# isp.net
KiCad netlist of a schematic drawn in EAGLE
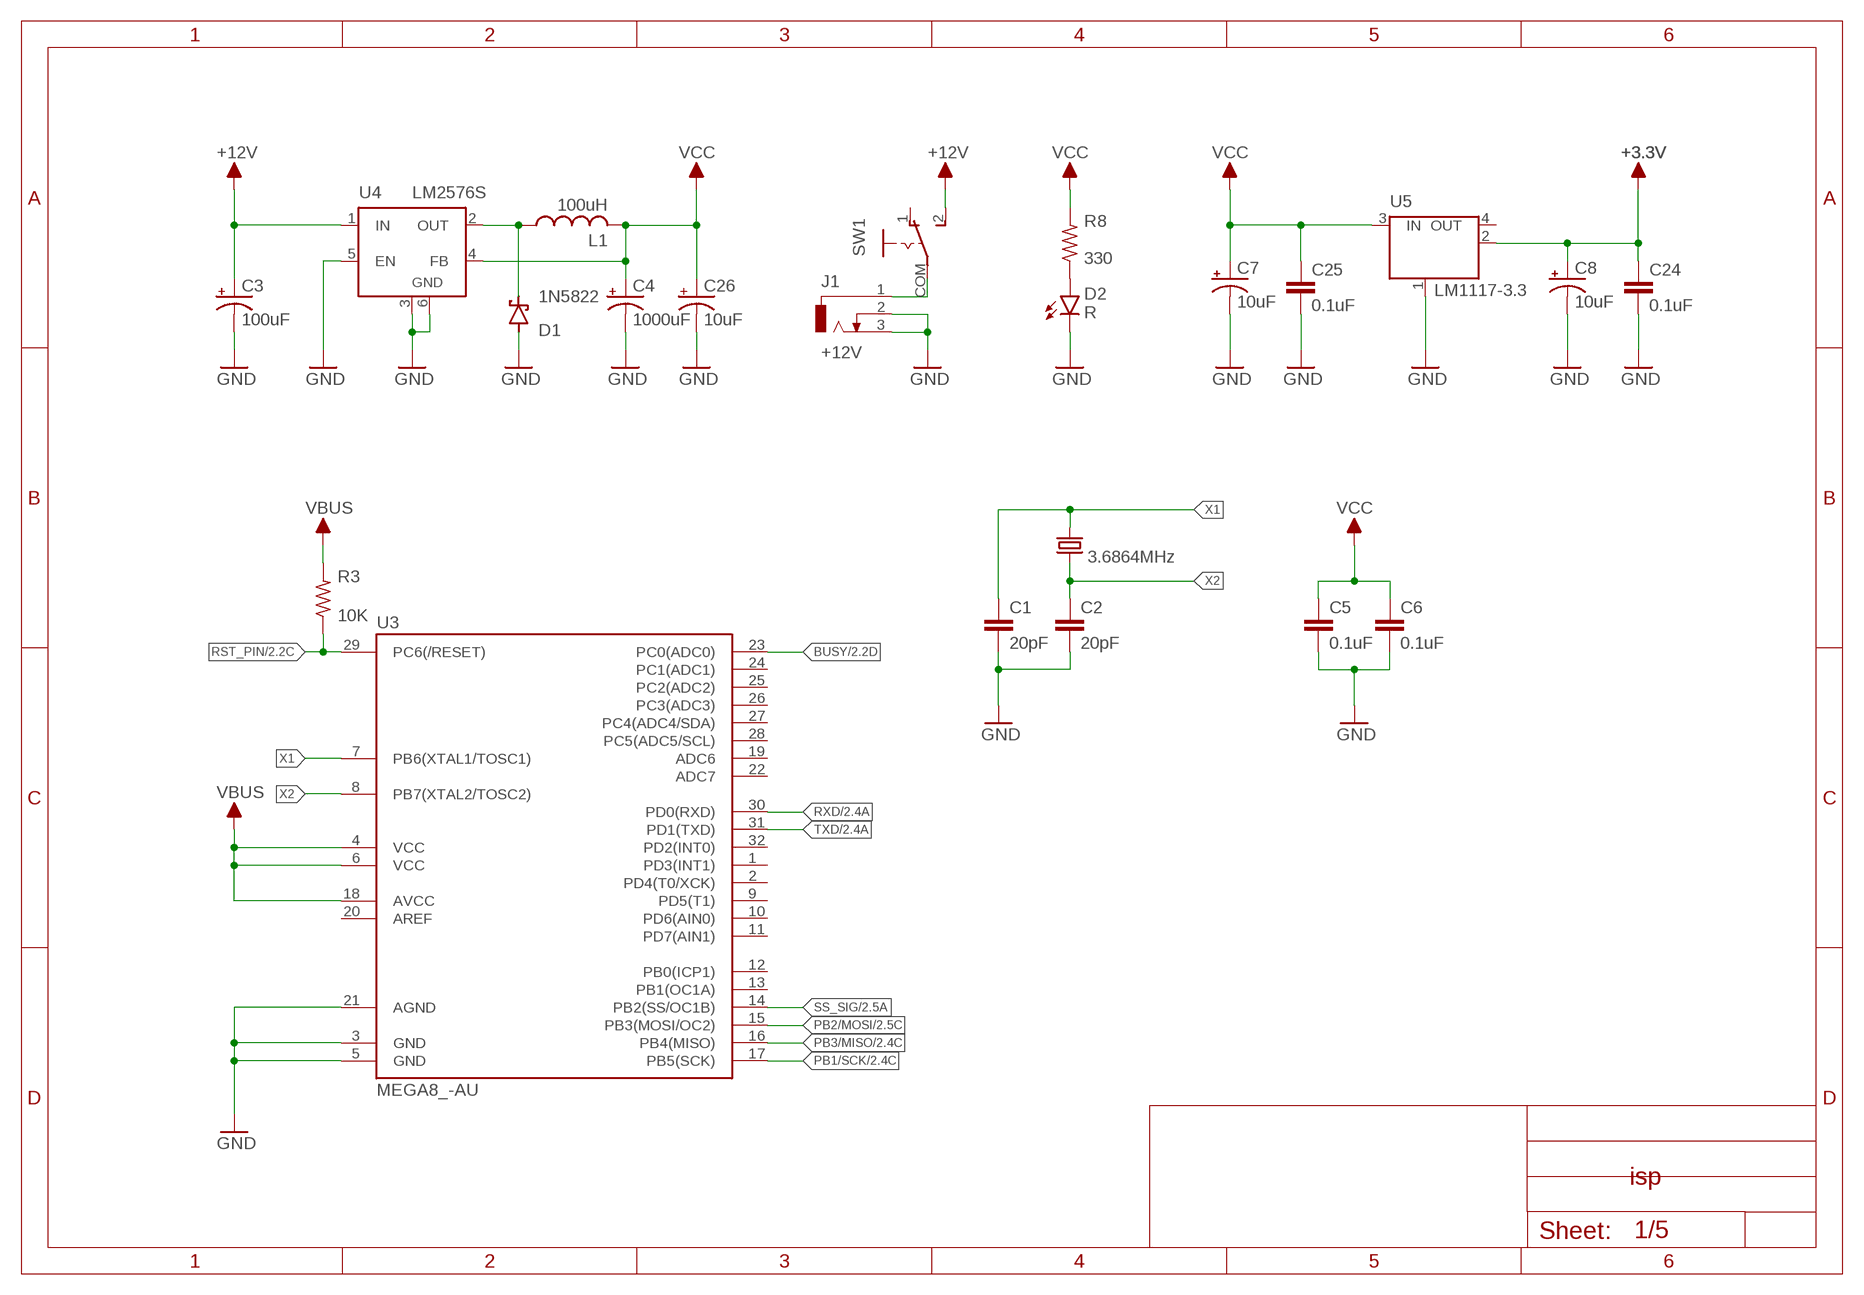
[diagram p0: schematic, sheet 1]
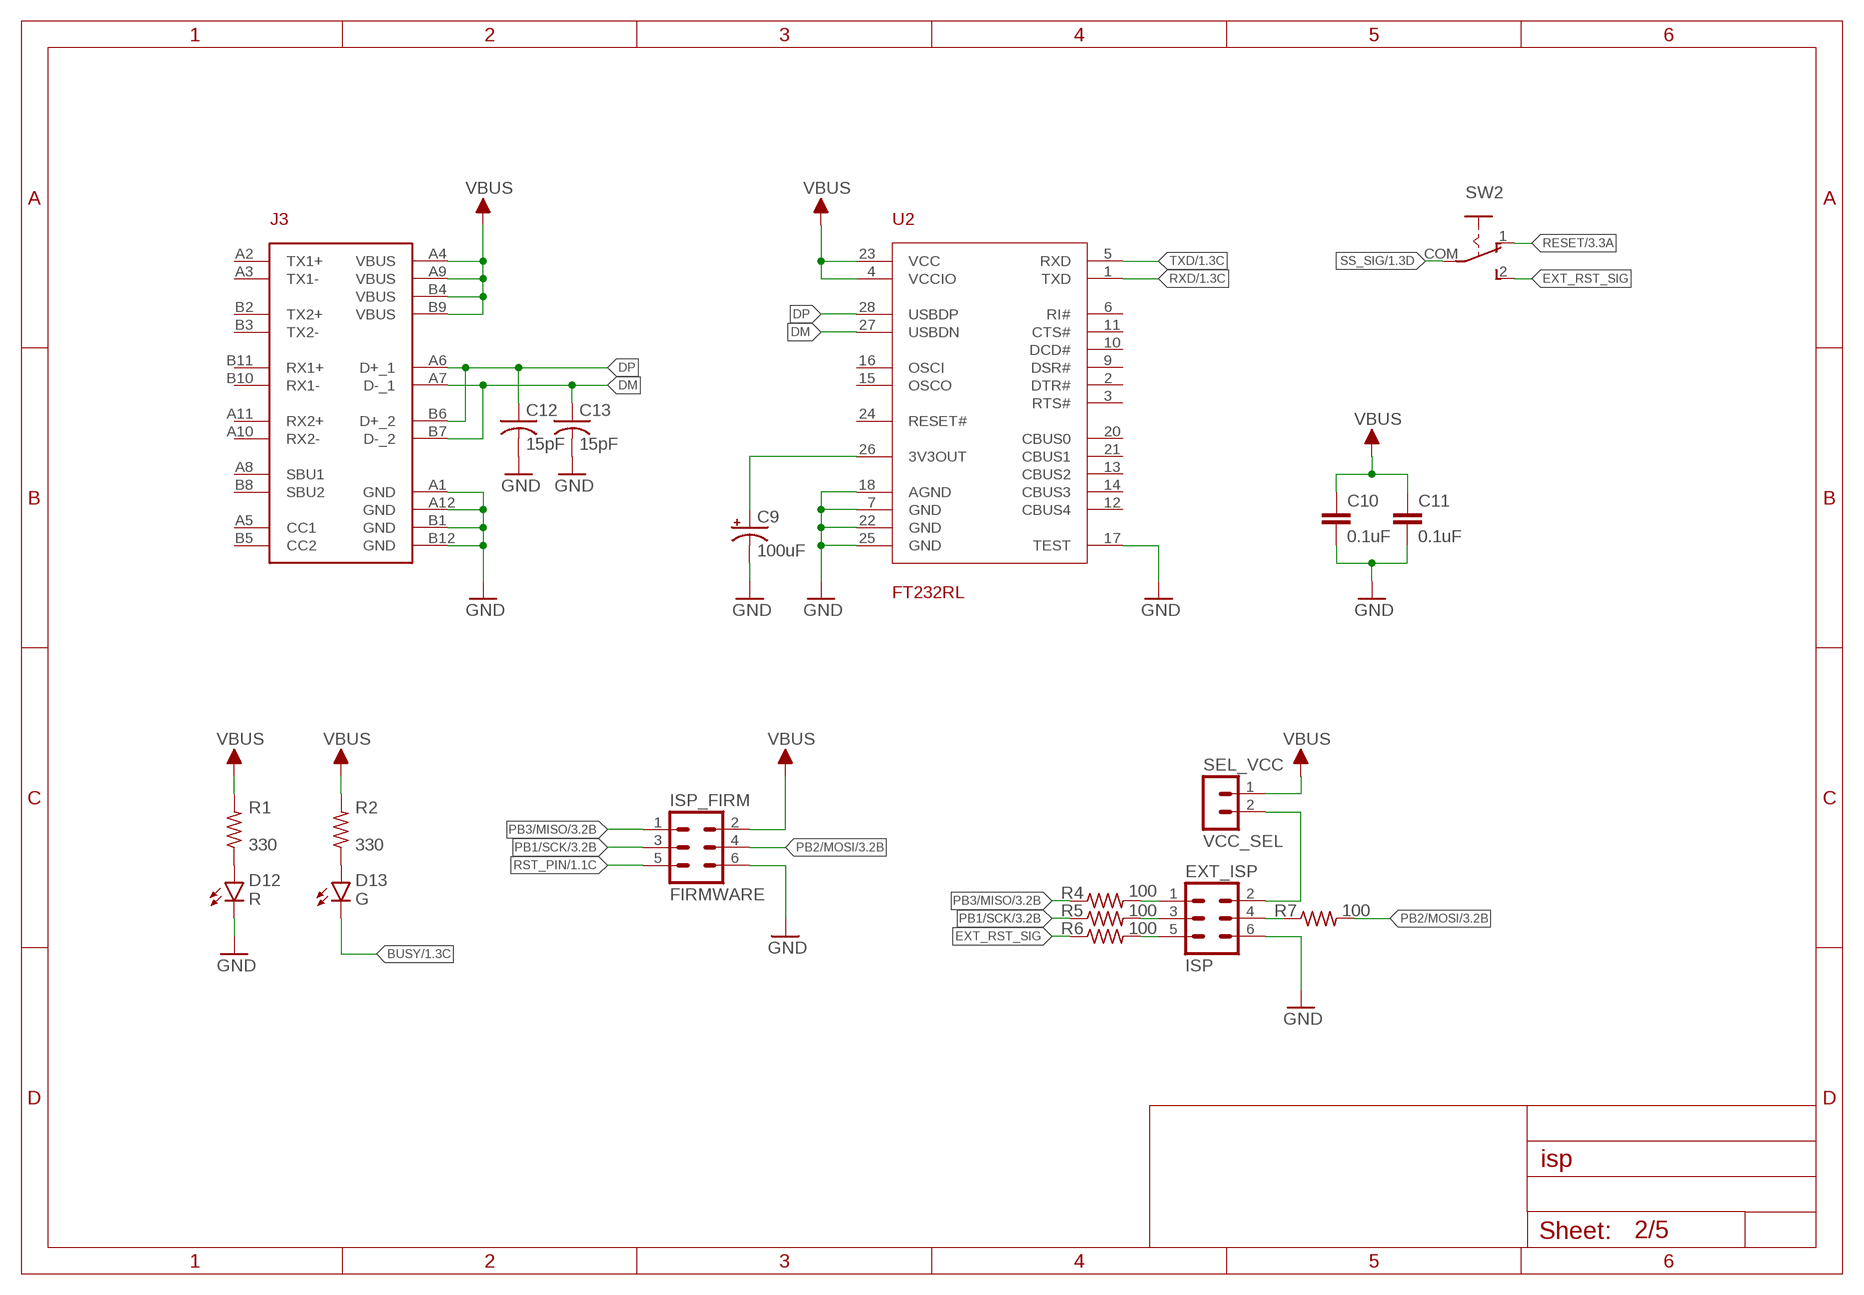
[diagram p1: schematic, sheet 2]
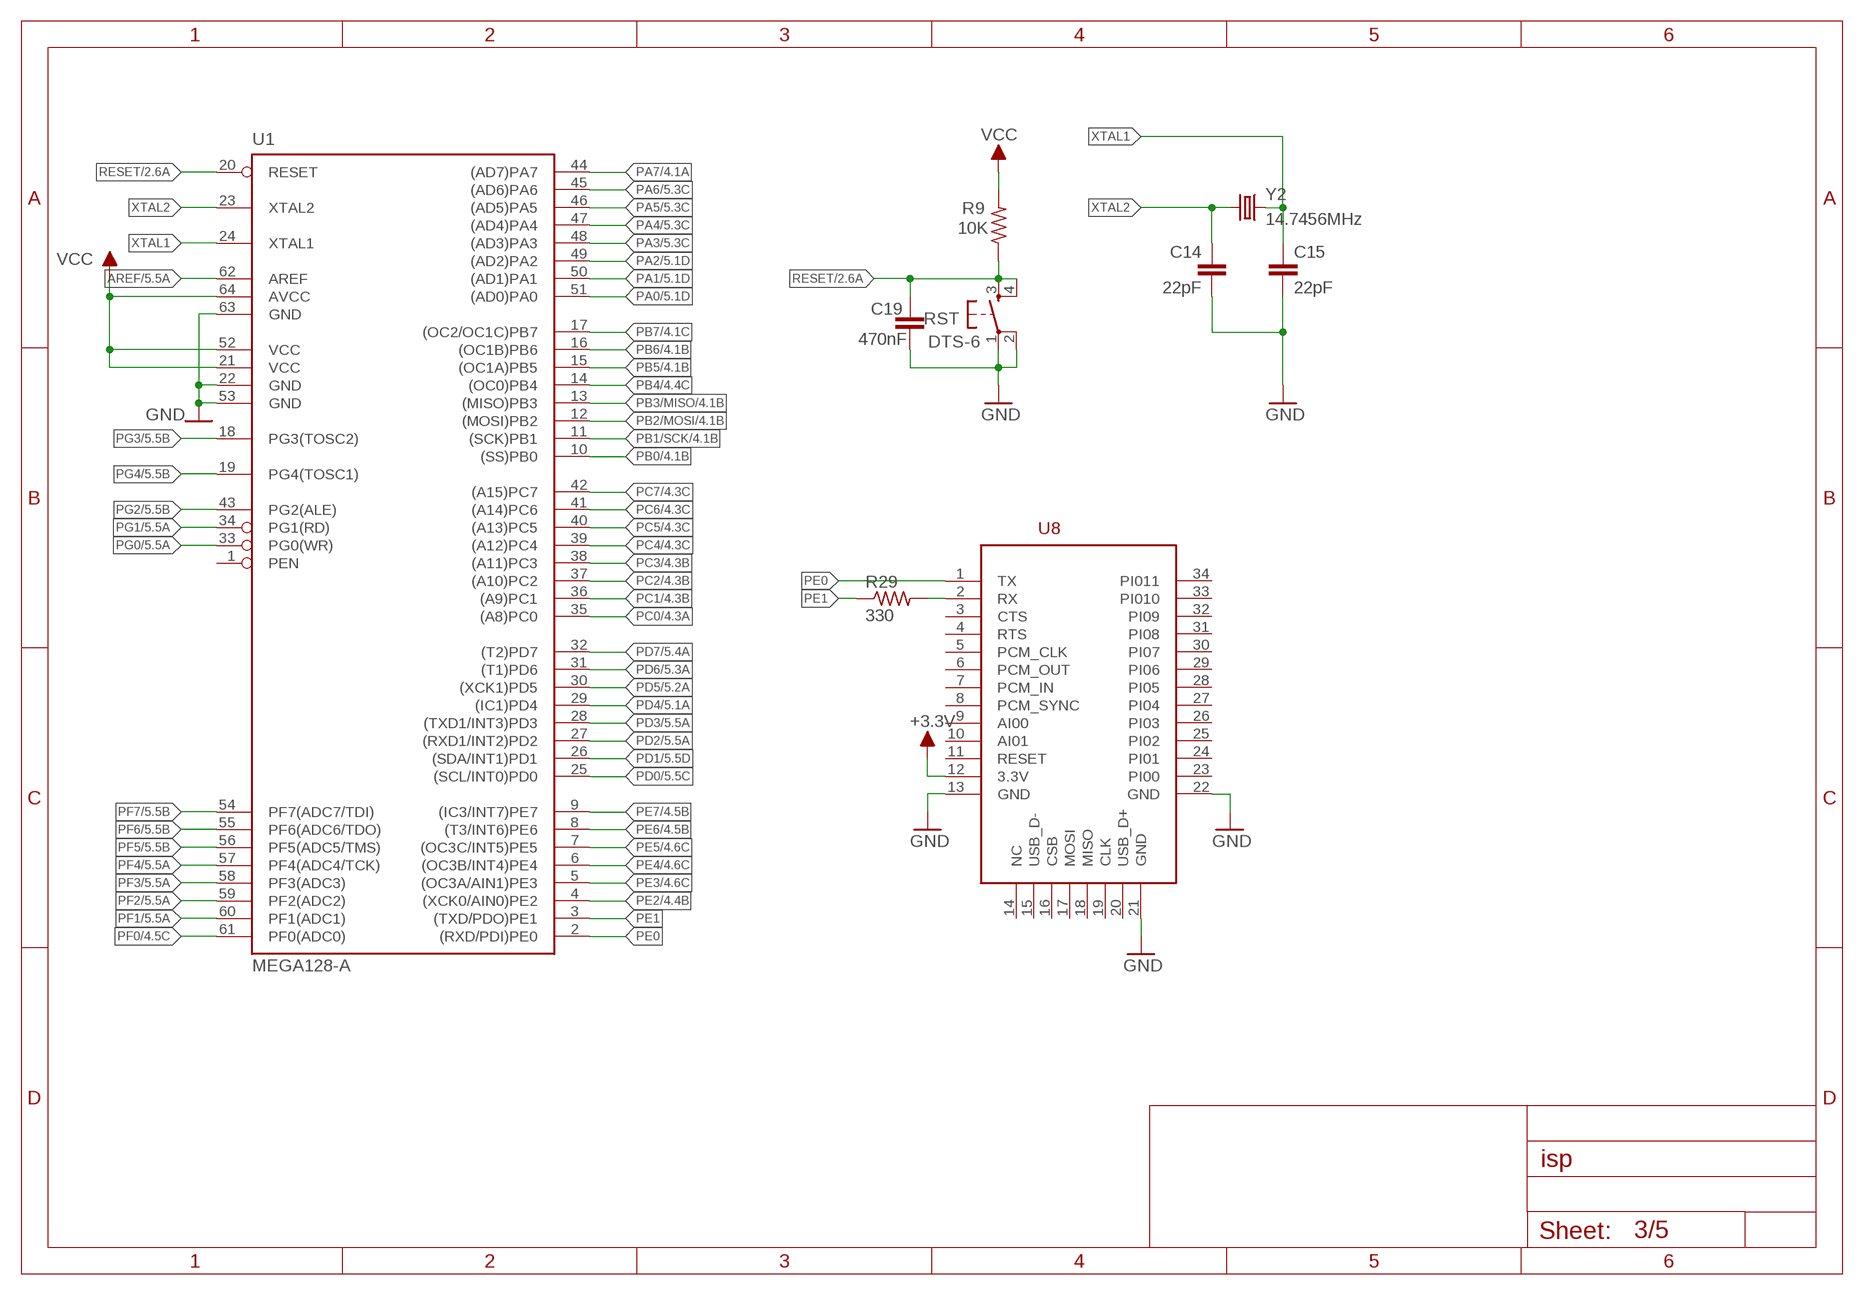
[diagram p2: schematic, sheet 3]
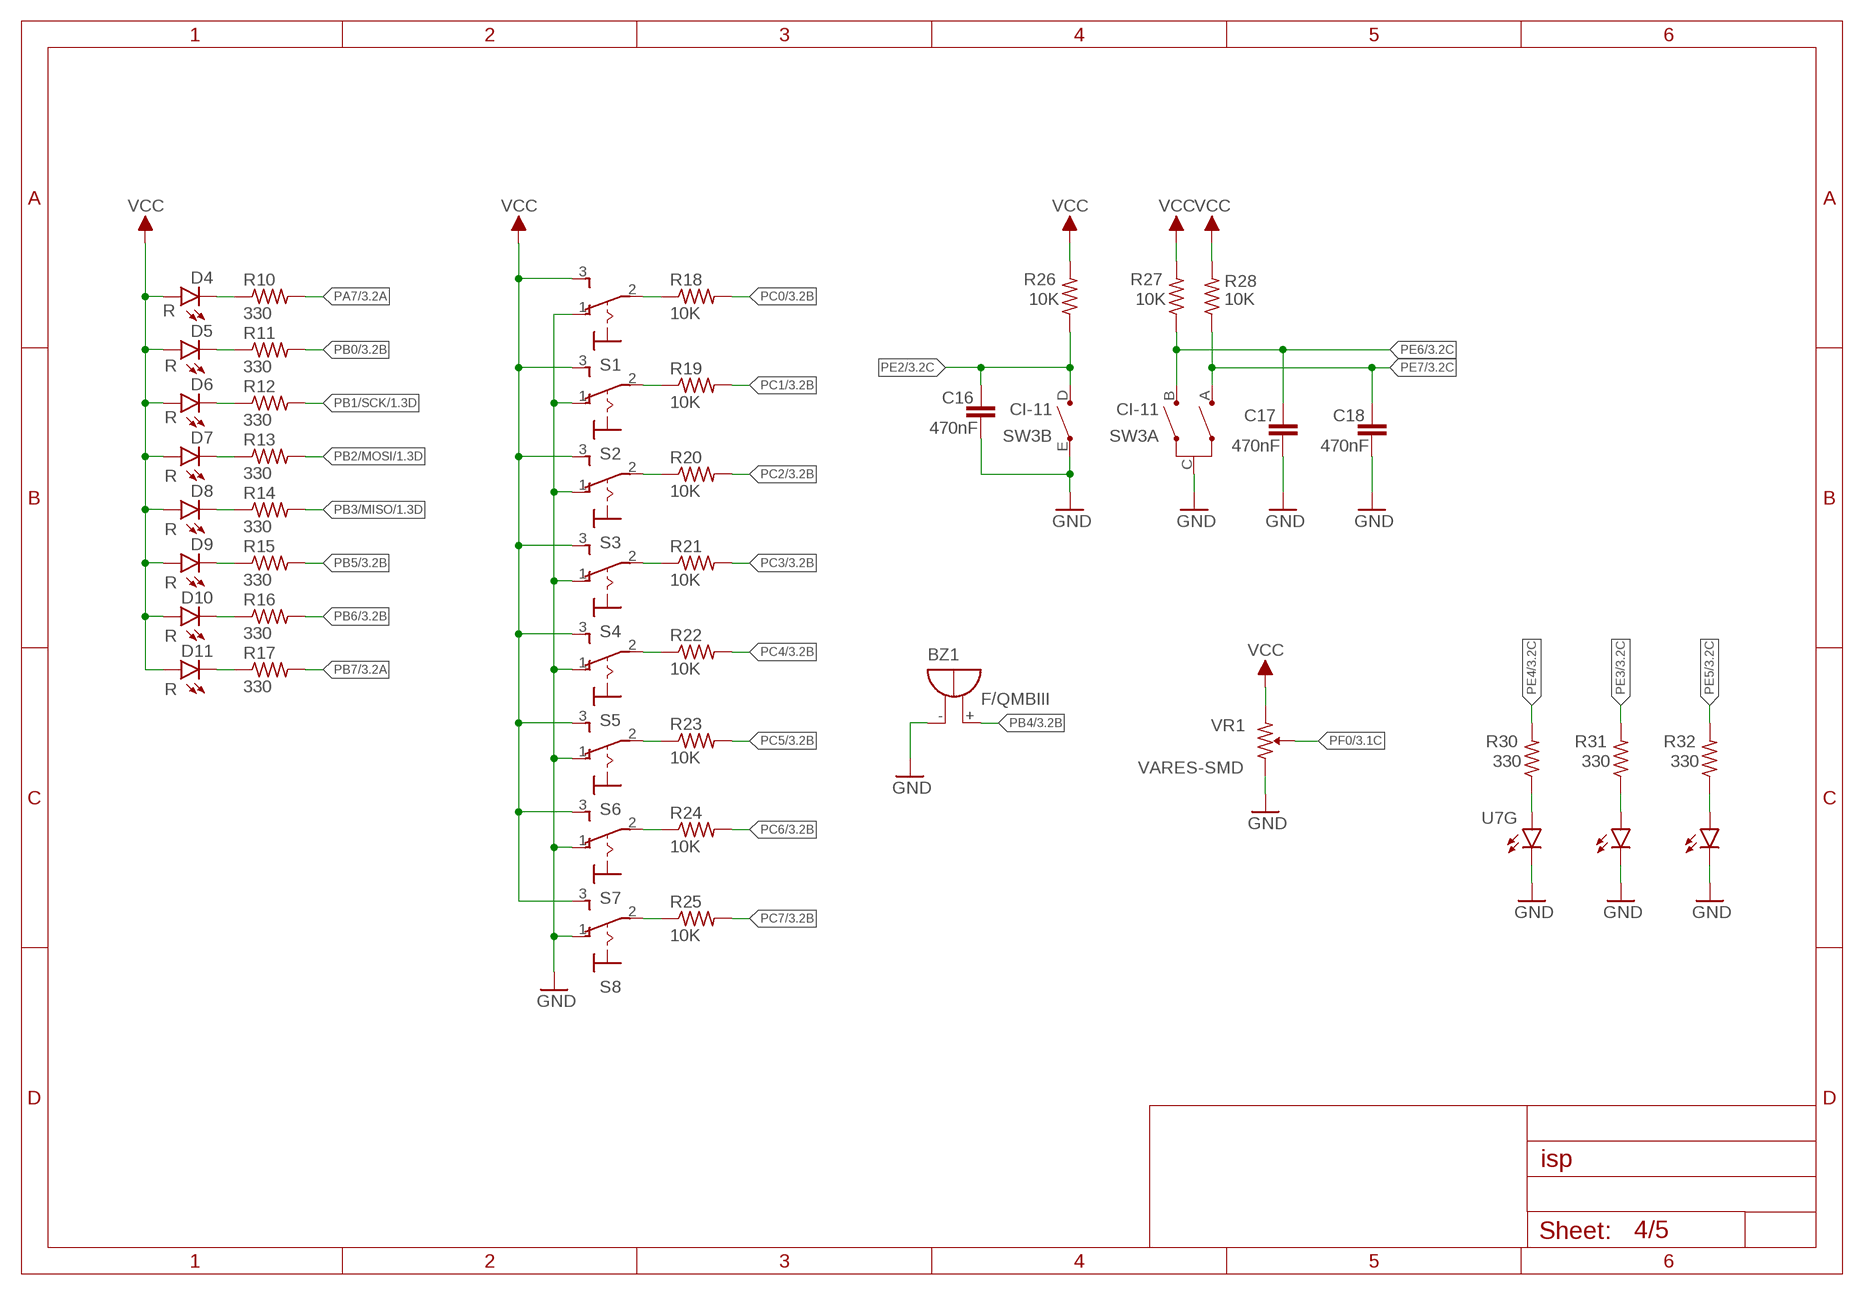
[diagram p3: schematic, sheet 4]
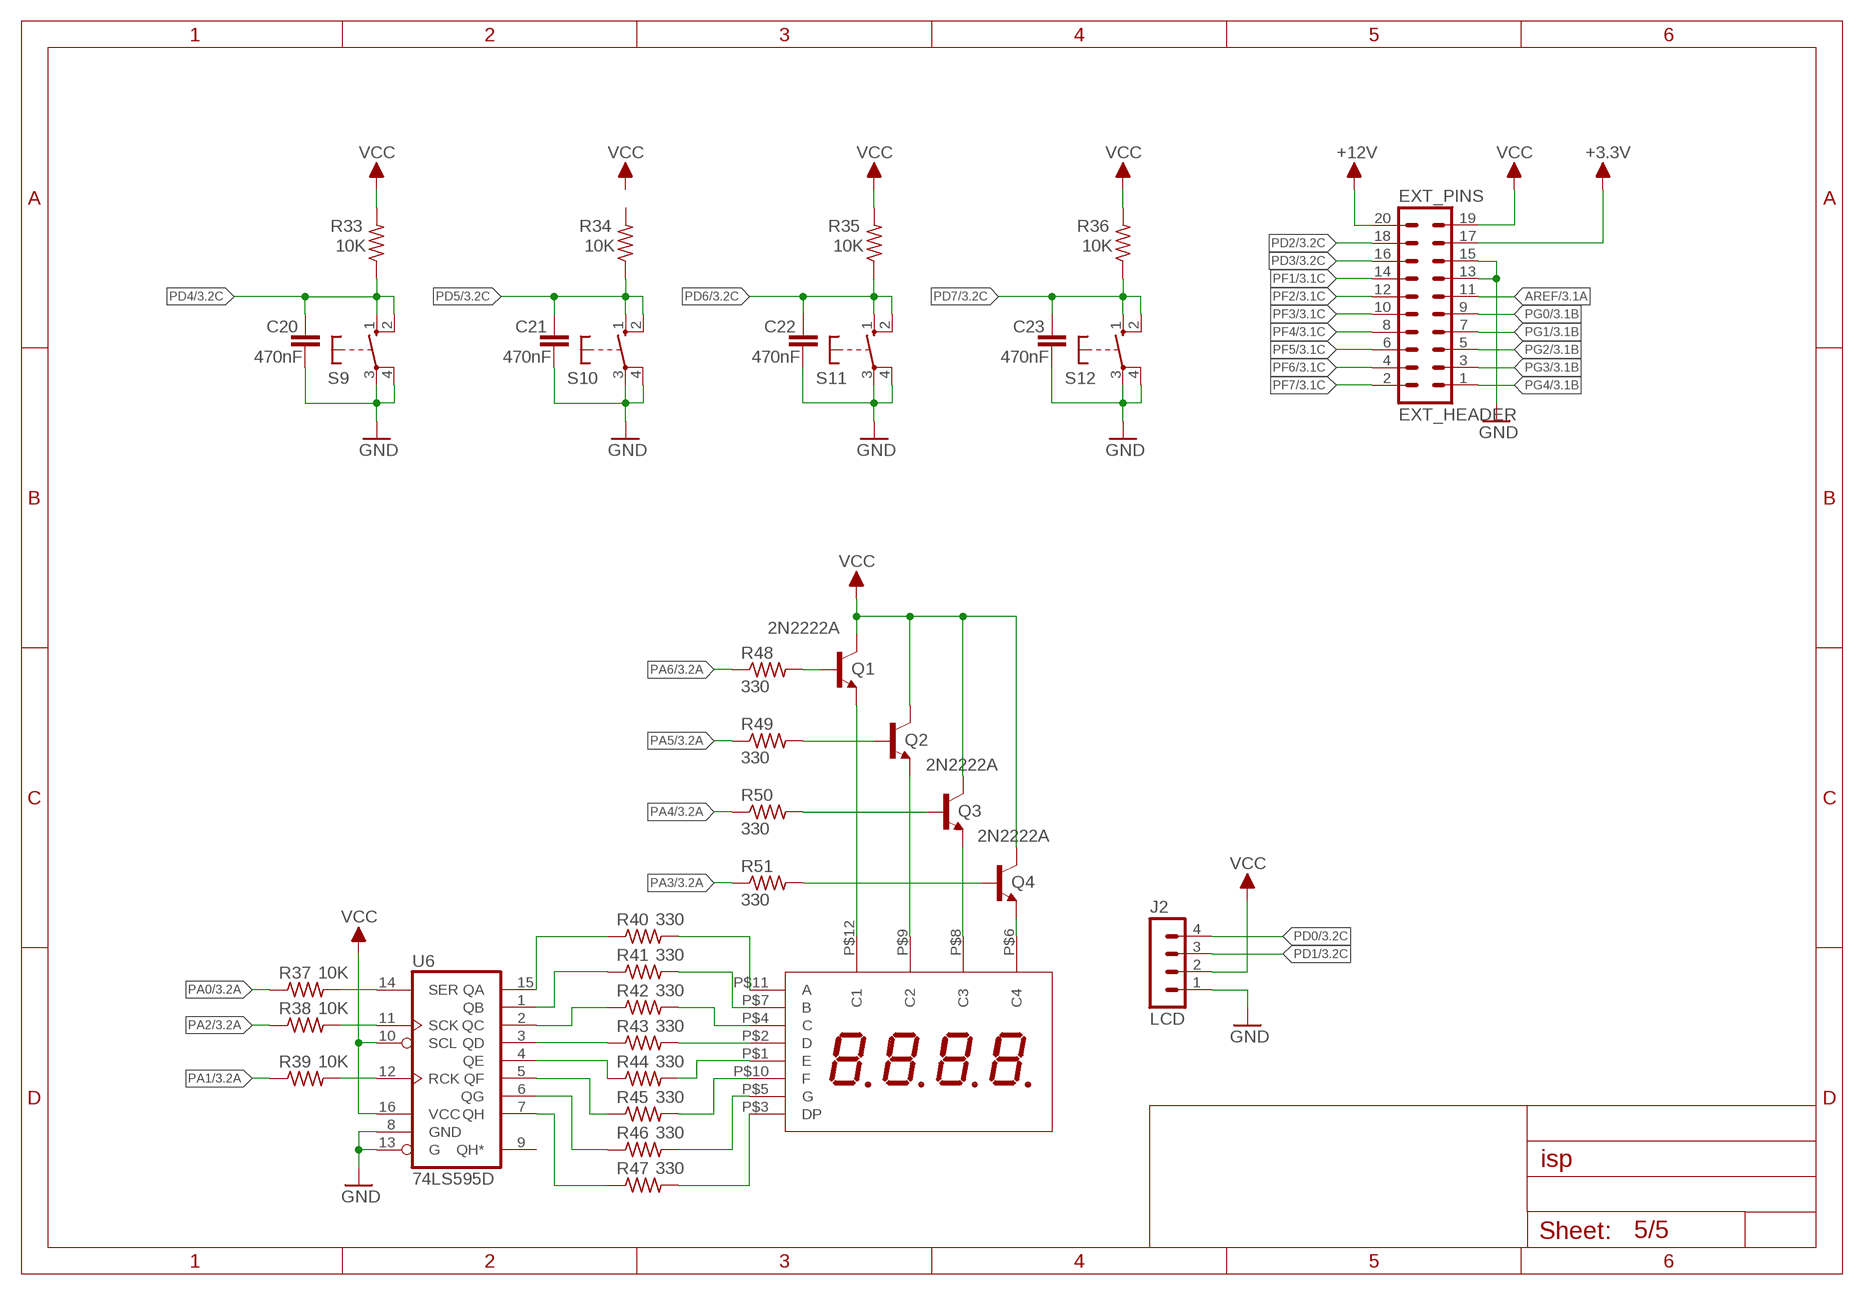
[diagram p4: schematic, sheet 5]

(export (version "E")
  (design (tool "Eeschema 10.0.6"))
  (components
    (comp (ref "BZ1")
      (value "F/QMBIII")
      (footprint "eagle-import:F_QMBIII")
      (libsource (lib "eagle-import") (part "F/QMBIII"))
    )
    (comp (ref "C16")
      (value "470nF")
      (footprint "eagle-import:C1206")
      (libsource (lib "eagle-import") (part "C-EUC1206"))
    )
    (comp (ref "C17")
      (value "470nF")
      (footprint "eagle-import:C1206")
      (libsource (lib "eagle-import") (part "C-EUC1206"))
    )
    (comp (ref "C18")
      (value "470nF")
      (footprint "eagle-import:C1206")
      (libsource (lib "eagle-import") (part "C-EUC1206"))
    )
    (comp (ref "D4")
      (value "R")
      (footprint "eagle-import:LED3MM")
      (libsource (lib "eagle-import") (part "LED3MM"))
    )
    (comp (ref "D5")
      (value "R")
      (footprint "eagle-import:LED3MM")
      (libsource (lib "eagle-import") (part "LED3MM"))
    )
    (comp (ref "D6")
      (value "R")
      (footprint "eagle-import:LED3MM")
      (libsource (lib "eagle-import") (part "LED3MM"))
    )
    (comp (ref "D7")
      (value "R")
      (footprint "eagle-import:LED3MM")
      (libsource (lib "eagle-import") (part "LED3MM"))
    )
    (comp (ref "D8")
      (value "R")
      (footprint "eagle-import:LED3MM")
      (libsource (lib "eagle-import") (part "LED3MM"))
    )
    (comp (ref "D9")
      (value "R")
      (footprint "eagle-import:LED3MM")
      (libsource (lib "eagle-import") (part "LED3MM"))
    )
    (comp (ref "D10")
      (value "R")
      (footprint "eagle-import:LED3MM")
      (libsource (lib "eagle-import") (part "LED3MM"))
    )
    (comp (ref "D11")
      (value "R")
      (footprint "eagle-import:LED3MM")
      (libsource (lib "eagle-import") (part "LED3MM"))
    )
    (comp (ref "R10")
      (value "330")
      (footprint "eagle-import:R0603")
      (libsource (lib "eagle-import") (part "R-US_R0603"))
    )
    (comp (ref "R11")
      (value "330")
      (footprint "eagle-import:R0603")
      (libsource (lib "eagle-import") (part "R-US_R0603"))
    )
    (comp (ref "R12")
      (value "330")
      (footprint "eagle-import:R0603")
      (libsource (lib "eagle-import") (part "R-US_R0603"))
    )
    (comp (ref "R13")
      (value "330")
      (footprint "eagle-import:R0603")
      (libsource (lib "eagle-import") (part "R-US_R0603"))
    )
    (comp (ref "R14")
      (value "330")
      (footprint "eagle-import:R0603")
      (libsource (lib "eagle-import") (part "R-US_R0603"))
    )
    (comp (ref "R15")
      (value "330")
      (footprint "eagle-import:R0603")
      (libsource (lib "eagle-import") (part "R-US_R0603"))
    )
    (comp (ref "R16")
      (value "330")
      (footprint "eagle-import:R0603")
      (libsource (lib "eagle-import") (part "R-US_R0603"))
    )
    (comp (ref "R17")
      (value "330")
      (footprint "eagle-import:R0603")
      (libsource (lib "eagle-import") (part "R-US_R0603"))
    )
    (comp (ref "R18")
      (value "10K")
      (footprint "eagle-import:R0603")
      (libsource (lib "eagle-import") (part "R-US_R0603"))
    )
    (comp (ref "R19")
      (value "10K")
      (footprint "eagle-import:R0603")
      (libsource (lib "eagle-import") (part "R-US_R0603"))
    )
    (comp (ref "R20")
      (value "10K")
      (footprint "eagle-import:R0603")
      (libsource (lib "eagle-import") (part "R-US_R0603"))
    )
    (comp (ref "R21")
      (value "10K")
      (footprint "eagle-import:R0603")
      (libsource (lib "eagle-import") (part "R-US_R0603"))
    )
    (comp (ref "R22")
      (value "10K")
      (footprint "eagle-import:R0603")
      (libsource (lib "eagle-import") (part "R-US_R0603"))
    )
    (comp (ref "R23")
      (value "10K")
      (footprint "eagle-import:R0603")
      (libsource (lib "eagle-import") (part "R-US_R0603"))
    )
    (comp (ref "R24")
      (value "10K")
      (footprint "eagle-import:R0603")
      (libsource (lib "eagle-import") (part "R-US_R0603"))
    )
    (comp (ref "R25")
      (value "10K")
      (footprint "eagle-import:R0603")
      (libsource (lib "eagle-import") (part "R-US_R0603"))
    )
    (comp (ref "R26")
      (value "10K")
      (footprint "eagle-import:R0603")
      (libsource (lib "eagle-import") (part "R-US_R0603"))
    )
    (comp (ref "R27")
      (value "10K")
      (footprint "eagle-import:R0603")
      (libsource (lib "eagle-import") (part "R-US_R0603"))
    )
    (comp (ref "R28")
      (value "10K")
      (footprint "eagle-import:R0603")
      (libsource (lib "eagle-import") (part "R-US_R0603"))
    )
    (comp (ref "R30")
      (value "330")
      (footprint "eagle-import:R0603")
      (libsource (lib "eagle-import") (part "R-US_R0603"))
    )
    (comp (ref "R31")
      (value "330")
      (footprint "eagle-import:R0603")
      (libsource (lib "eagle-import") (part "R-US_R0603"))
    )
    (comp (ref "R32")
      (value "330")
      (footprint "eagle-import:R0603")
      (libsource (lib "eagle-import") (part "R-US_R0603"))
    )
    (comp (ref "S1")
      (value "M9040P")
      (footprint "eagle-import:M9040P")
      (libsource (lib "eagle-import") (part "M9040P"))
    )
    (comp (ref "S2")
      (value "M9040P")
      (footprint "eagle-import:M9040P")
      (libsource (lib "eagle-import") (part "M9040P"))
    )
    (comp (ref "S3")
      (value "M9040P")
      (footprint "eagle-import:M9040P")
      (libsource (lib "eagle-import") (part "M9040P"))
    )
    (comp (ref "S4")
      (value "M9040P")
      (footprint "eagle-import:M9040P")
      (libsource (lib "eagle-import") (part "M9040P"))
    )
    (comp (ref "S5")
      (value "M9040P")
      (footprint "eagle-import:M9040P")
      (libsource (lib "eagle-import") (part "M9040P"))
    )
    (comp (ref "S6")
      (value "M9040P")
      (footprint "eagle-import:M9040P")
      (libsource (lib "eagle-import") (part "M9040P"))
    )
    (comp (ref "S7")
      (value "M9040P")
      (footprint "eagle-import:M9040P")
      (libsource (lib "eagle-import") (part "M9040P"))
    )
    (comp (ref "S8")
      (value "M9040P")
      (footprint "eagle-import:M9040P")
      (libsource (lib "eagle-import") (part "M9040P"))
    )
    (comp (ref "SW3")
      (value "CI-11")
      (footprint "eagle-import:CI-11")
      (libsource (lib "eagle-import") (part "CI-11"))
    )
    (comp (ref "U7")
      (value "LP2C63-ST-RGB-SR0")
      (footprint "eagle-import:LP2C63-ST-RGB-SR0")
      (libsource (lib "eagle-import") (part "LP2C63-ST-RGB-SR0"))
    )
    (comp (ref "VR1")
      (value "VARES-SMD")
      (footprint "eagle-import:VARES-SMD")
      (libsource (lib "eagle-import") (part "VARES-SMD"))
    )
    (comp (ref "C14")
      (value "22pF")
      (footprint "eagle-import:C0603")
      (libsource (lib "eagle-import") (part "C-EUC0603"))
    )
    (comp (ref "C15")
      (value "22pF")
      (footprint "eagle-import:C0603")
      (libsource (lib "eagle-import") (part "C-EUC0603"))
    )
    (comp (ref "C19")
      (value "470nF")
      (footprint "eagle-import:C1206")
      (libsource (lib "eagle-import") (part "C-EUC1206"))
    )
    (comp (ref "R9")
      (value "10K")
      (footprint "eagle-import:R0603")
      (libsource (lib "eagle-import") (part "R-US_R0603"))
    )
    (comp (ref "R29")
      (value "330")
      (footprint "eagle-import:R0603")
      (libsource (lib "eagle-import") (part "R-US_R0603"))
    )
    (comp (ref "RST")
      (value "DTS-6")
      (footprint "eagle-import:DTS-6")
      (libsource (lib "eagle-import") (part "DTS-6"))
    )
    (comp (ref "U1")
      (value "MEGA128-A")
      (footprint "eagle-import:TQFP64")
      (fields (field (name "MPN") "ATMEGA128-16AU"))
      (libsource (lib "eagle-import") (part "MEGA128-A"))
    )
    (comp (ref "U8")
      (value "HC06-SMD")
      (footprint "eagle-import:HC06-SMD")
      (libsource (lib "eagle-import") (part "HC06-SMD"))
    )
    (comp (ref "Y2")
      (value "14.7456MHz")
      (footprint "eagle-import:HC49UP")
      (libsource (lib "eagle-import") (part "CRYSTALHC49UP"))
    )
    (comp (ref "C1")
      (value "20pF")
      (footprint "eagle-import:C0603")
      (libsource (lib "eagle-import") (part "C-EUC0603"))
    )
    (comp (ref "C2")
      (value "20pF")
      (footprint "eagle-import:C0603")
      (libsource (lib "eagle-import") (part "C-EUC0603"))
    )
    (comp (ref "C3")
      (value "100uF")
      (footprint "eagle-import:153CLV-0807")
      (libsource (lib "eagle-import") (part "CPOL-US153CLV-0807"))
    )
    (comp (ref "C4")
      (value "1000uF")
      (footprint "eagle-import:MVG_K14")
      (libsource (lib "eagle-import") (part "MVG_K14"))
    )
    (comp (ref "C5")
      (value "0.1uF")
      (footprint "eagle-import:C0603")
      (libsource (lib "eagle-import") (part "C-EUC0603"))
    )
    (comp (ref "C6")
      (value "0.1uF")
      (footprint "eagle-import:C0603")
      (libsource (lib "eagle-import") (part "C-EUC0603"))
    )
    (comp (ref "C7")
      (value "10uF")
      (footprint "eagle-import:153CLV-0605")
      (libsource (lib "eagle-import") (part "CPOL-US153CLV-0605"))
    )
    (comp (ref "C8")
      (value "10uF")
      (footprint "eagle-import:153CLV-0605")
      (libsource (lib "eagle-import") (part "CPOL-US153CLV-0605"))
    )
    (comp (ref "C24")
      (value "0.1uF")
      (footprint "eagle-import:C0603")
      (libsource (lib "eagle-import") (part "C-EUC0603"))
    )
    (comp (ref "C25")
      (value "0.1uF")
      (footprint "eagle-import:C0603")
      (libsource (lib "eagle-import") (part "C-EUC0603"))
    )
    (comp (ref "C26")
      (value "10uF")
      (footprint "eagle-import:153CLV-0605")
      (libsource (lib "eagle-import") (part "CPOL-US153CLV-0605"))
    )
    (comp (ref "D1")
      (value "1N5822")
      (footprint "eagle-import:DO201T15")
      (libsource (lib "eagle-import") (part "15KEXXD"))
    )
    (comp (ref "D2")
      (value "R")
      (footprint "eagle-import:LED3MM")
      (libsource (lib "eagle-import") (part "LED3MM"))
    )
    (comp (ref "J1")
      (value "+12V")
      (footprint "eagle-import:DCJ0303")
      (libsource (lib "eagle-import") (part "DCJ0303"))
    )
    (comp (ref "L1")
      (value "100uH")
      (footprint "eagle-import:212-032T2")
      (libsource (lib "eagle-import") (part "SC1280S"))
    )
    (comp (ref "R3")
      (value "10K")
      (footprint "eagle-import:R0603")
      (libsource (lib "eagle-import") (part "R-US_R0603"))
    )
    (comp (ref "R8")
      (value "330")
      (footprint "eagle-import:R0603")
      (libsource (lib "eagle-import") (part "R-US_R0603"))
    )
    (comp (ref "SW1")
      (value "SLIDE-SW-DIP")
      (footprint "eagle-import:SLIDE-SW-DIP-SHIELD")
      (libsource (lib "eagle-import") (part "SLIDE-SW-DIP"))
    )
    (comp (ref "U3")
      (value "MEGA8_-AU")
      (footprint "eagle-import:TQFP32-08")
      (libsource (lib "eagle-import") (part "MEGA8_-AU"))
    )
    (comp (ref "U4")
      (value "LM2576S")
      (footprint "eagle-import:TO263-5")
      (libsource (lib "eagle-import") (part "LM2596S"))
    )
    (comp (ref "U5")
      (value "LM1117-3.3")
      (footprint "eagle-import:SOT223")
      (libsource (lib "eagle-import") (part "MC33269ST-3.3T3"))
    )
    (comp (ref "Y1")
      (value "3.6864MHz")
      (footprint "eagle-import:HC49UP")
      (libsource (lib "eagle-import") (part "CRYSTALHC49UP"))
    )
    (comp (ref "C20")
      (value "470nF")
      (footprint "eagle-import:C1206")
      (libsource (lib "eagle-import") (part "C-EUC1206"))
    )
    (comp (ref "C21")
      (value "470nF")
      (footprint "eagle-import:C1206")
      (libsource (lib "eagle-import") (part "C-EUC1206"))
    )
    (comp (ref "C22")
      (value "470nF")
      (footprint "eagle-import:C1206")
      (libsource (lib "eagle-import") (part "C-EUC1206"))
    )
    (comp (ref "C23")
      (value "470nF")
      (footprint "eagle-import:C1206")
      (libsource (lib "eagle-import") (part "C-EUC1206"))
    )
    (comp (ref "D3")
      (value "4CH_FND-DIP")
      (footprint "eagle-import:4CH_FND-DIP")
      (libsource (lib "eagle-import") (part "4CH_FND-DIP"))
    )
    (comp (ref "EXT_PINS")
      (value "EXT_HEADER")
      (footprint "eagle-import:MA10-2")
      (libsource (lib "eagle-import") (part "MA10-2"))
    )
    (comp (ref "J2")
      (value "LCD")
      (footprint "eagle-import:MA04-1")
      (libsource (lib "eagle-import") (part "MA04-1"))
    )
    (comp (ref "Q1")
      (value "2N2222A")
      (footprint "eagle-import:TO92-EBC")
      (libsource (lib "eagle-import") (part "-NPN-TO92-EBC"))
    )
    (comp (ref "Q2")
      (value "2N2222A")
      (footprint "eagle-import:TO92-EBC")
      (libsource (lib "eagle-import") (part "-NPN-TO92-EBC"))
    )
    (comp (ref "Q3")
      (value "2N2222A")
      (footprint "eagle-import:TO92-EBC")
      (libsource (lib "eagle-import") (part "-NPN-TO92-EBC"))
    )
    (comp (ref "Q4")
      (value "2N2222A")
      (footprint "eagle-import:TO92-EBC")
      (libsource (lib "eagle-import") (part "-NPN-TO92-EBC"))
    )
    (comp (ref "R33")
      (value "10K")
      (footprint "eagle-import:R0603")
      (libsource (lib "eagle-import") (part "R-US_R0603"))
    )
    (comp (ref "R34")
      (value "10K")
      (footprint "eagle-import:R0603")
      (libsource (lib "eagle-import") (part "R-US_R0603"))
    )
    (comp (ref "R35")
      (value "10K")
      (footprint "eagle-import:R0603")
      (libsource (lib "eagle-import") (part "R-US_R0603"))
    )
    (comp (ref "R36")
      (value "10K")
      (footprint "eagle-import:R0603")
      (libsource (lib "eagle-import") (part "R-US_R0603"))
    )
    (comp (ref "R37")
      (value "10K")
      (footprint "eagle-import:R0603")
      (libsource (lib "eagle-import") (part "R-US_R0603"))
    )
    (comp (ref "R38")
      (value "10K")
      (footprint "eagle-import:R0603")
      (libsource (lib "eagle-import") (part "R-US_R0603"))
    )
    (comp (ref "R39")
      (value "10K")
      (footprint "eagle-import:R0603")
      (libsource (lib "eagle-import") (part "R-US_R0603"))
    )
    (comp (ref "R40")
      (value "330")
      (footprint "eagle-import:R0603")
      (libsource (lib "eagle-import") (part "R-US_R0603"))
    )
    (comp (ref "R41")
      (value "330")
      (footprint "eagle-import:R0603")
      (libsource (lib "eagle-import") (part "R-US_R0603"))
    )
    (comp (ref "R42")
      (value "330")
      (footprint "eagle-import:R0603")
      (libsource (lib "eagle-import") (part "R-US_R0603"))
    )
    (comp (ref "R43")
      (value "330")
      (footprint "eagle-import:R0603")
      (libsource (lib "eagle-import") (part "R-US_R0603"))
    )
    (comp (ref "R44")
      (value "330")
      (footprint "eagle-import:R0603")
      (libsource (lib "eagle-import") (part "R-US_R0603"))
    )
    (comp (ref "R45")
      (value "330")
      (footprint "eagle-import:R0603")
      (libsource (lib "eagle-import") (part "R-US_R0603"))
    )
    (comp (ref "R46")
      (value "330")
      (footprint "eagle-import:R0603")
      (libsource (lib "eagle-import") (part "R-US_R0603"))
    )
    (comp (ref "R47")
      (value "330")
      (footprint "eagle-import:R0603")
      (libsource (lib "eagle-import") (part "R-US_R0603"))
    )
    (comp (ref "R48")
      (value "330")
      (footprint "eagle-import:R0603")
      (libsource (lib "eagle-import") (part "R-US_R0603"))
    )
    (comp (ref "R49")
      (value "330")
      (footprint "eagle-import:R0603")
      (libsource (lib "eagle-import") (part "R-US_R0603"))
    )
    (comp (ref "R50")
      (value "330")
      (footprint "eagle-import:R0603")
      (libsource (lib "eagle-import") (part "R-US_R0603"))
    )
    (comp (ref "R51")
      (value "330")
      (footprint "eagle-import:R0603")
      (libsource (lib "eagle-import") (part "R-US_R0603"))
    )
    (comp (ref "S9")
      (value "RACON12")
      (footprint "eagle-import:RACON12")
      (libsource (lib "eagle-import") (part "RACON12"))
    )
    (comp (ref "S10")
      (value "RACON12")
      (footprint "eagle-import:RACON12")
      (libsource (lib "eagle-import") (part "RACON12"))
    )
    (comp (ref "S11")
      (value "RACON12")
      (footprint "eagle-import:RACON12")
      (libsource (lib "eagle-import") (part "RACON12"))
    )
    (comp (ref "S12")
      (value "RACON12")
      (footprint "eagle-import:RACON12")
      (libsource (lib "eagle-import") (part "RACON12"))
    )
    (comp (ref "U6")
      (value "74LS595D")
      (footprint "eagle-import:SO16")
      (libsource (lib "eagle-import") (part "74595DLS"))
    )
    (comp (ref "C9")
      (value "100uF")
      (footprint "eagle-import:153CLV-0807")
      (libsource (lib "eagle-import") (part "CPOL-US153CLV-0807"))
    )
    (comp (ref "C10")
      (value "0.1uF")
      (footprint "eagle-import:C0603")
      (libsource (lib "eagle-import") (part "C-EUC0603"))
    )
    (comp (ref "C11")
      (value "0.1uF")
      (footprint "eagle-import:C0603")
      (libsource (lib "eagle-import") (part "C-EUC0603"))
    )
    (comp (ref "C12")
      (value "15pF")
      (footprint "eagle-import:C0603")
      (libsource (lib "eagle-import") (part "C-USC0603"))
    )
    (comp (ref "C13")
      (value "15pF")
      (footprint "eagle-import:C0603")
      (libsource (lib "eagle-import") (part "C-USC0603"))
    )
    (comp (ref "D12")
      (value "R")
      (footprint "eagle-import:LED3MM")
      (libsource (lib "eagle-import") (part "LED3MM"))
    )
    (comp (ref "D13")
      (value "G")
      (footprint "eagle-import:LED3MM")
      (libsource (lib "eagle-import") (part "LED3MM"))
    )
    (comp (ref "EXT_ISP")
      (value "ISP")
      (footprint "eagle-import:ML6")
      (libsource (lib "eagle-import") (part "ML6"))
    )
    (comp (ref "ISP_FIRM")
      (value "FIRMWARE")
      (footprint "eagle-import:MA03-2")
      (libsource (lib "eagle-import") (part "MA03-2"))
    )
    (comp (ref "J3")
      (value "USB-C-SMD")
      (footprint "eagle-import:USB3.1-C-SMD")
      (libsource (lib "eagle-import") (part "USB-C-SMD"))
    )
    (comp (ref "R1")
      (value "330")
      (footprint "eagle-import:R0603")
      (libsource (lib "eagle-import") (part "R-US_R0603"))
    )
    (comp (ref "R2")
      (value "330")
      (footprint "eagle-import:R0603")
      (libsource (lib "eagle-import") (part "R-US_R0603"))
    )
    (comp (ref "R4")
      (value "100")
      (footprint "eagle-import:R0603")
      (libsource (lib "eagle-import") (part "R-US_R0603"))
    )
    (comp (ref "R5")
      (value "100")
      (footprint "eagle-import:R0603")
      (libsource (lib "eagle-import") (part "R-US_R0603"))
    )
    (comp (ref "R6")
      (value "100")
      (footprint "eagle-import:R0603")
      (libsource (lib "eagle-import") (part "R-US_R0603"))
    )
    (comp (ref "R7")
      (value "100")
      (footprint "eagle-import:R0603")
      (libsource (lib "eagle-import") (part "R-US_R0603"))
    )
    (comp (ref "SEL_VCC")
      (value "VCC_SEL")
      (footprint "eagle-import:MA02-1")
      (libsource (lib "eagle-import") (part "MA02-1"))
    )
    (comp (ref "SW2")
      (value "SLIDE-SW-DIP")
      (footprint "eagle-import:SLIDE-SW-DIP-SHIELD")
      (libsource (lib "eagle-import") (part "SLIDE-SW-DIP"))
    )
    (comp (ref "U2")
      (value "FT232RL")
      (footprint "eagle-import:SSOP28")
      (libsource (lib "eagle-import") (part "FT232RL"))
    )
  )
  (nets
    (net (code "1") (name "+3.3V") (class "Default")
      (node (ref "C24") (pin "1") (pinfunction "1_1") (pintype "passive"))
      (node (ref "C8") (pin "+") (pinfunction "+_+") (pintype "passive"))
      (node (ref "EXT_PINS") (pin "17") (pinfunction "17_17") (pintype "passive"))
      (node (ref "U5") (pin "2") (pinfunction "OUT_2") (pintype "passive"))
      (node (ref "U8") (pin "12") (pinfunction "3.3V_12") (pintype "power_in"))
    )
    (net (code "2") (name "+12V") (class "Default")
      (node (ref "C3") (pin "+") (pinfunction "+_+") (pintype "passive"))
      (node (ref "EXT_PINS") (pin "20") (pinfunction "20_20") (pintype "passive"))
      (node (ref "SW1") (pin "2") (pinfunction "2_2") (pintype "passive"))
      (node (ref "U4") (pin "1") (pinfunction "IN_1") (pintype "input"))
    )
    (net (code "3") (name "AREF") (class "Default")
      (node (ref "EXT_PINS") (pin "11") (pinfunction "11_11") (pintype "passive"))
      (node (ref "U1") (pin "62") (pinfunction "AREF_62") (pintype "passive"))
    )
    (net (code "4") (name "BUSY") (class "Default")
      (node (ref "D13") (pin "K") (pinfunction "C_K") (pintype "passive"))
      (node (ref "U3") (pin "23") (pinfunction "PC0(ADC0)_23") (pintype "bidirectional"))
    )
    (net (code "5") (name "DM") (class "Default")
      (node (ref "C13") (pin "1") (pinfunction "1_1") (pintype "passive"))
      (node (ref "J3") (pin "A7") (pinfunction "D-_1_A7") (pintype "bidirectional"))
      (node (ref "J3") (pin "B7") (pinfunction "D-_2_B7") (pintype "bidirectional"))
      (node (ref "U2") (pin "27") (pinfunction "USBDN_27") (pintype "bidirectional"))
    )
    (net (code "6") (name "DP") (class "Default")
      (node (ref "C12") (pin "1") (pinfunction "1_1") (pintype "passive"))
      (node (ref "J3") (pin "A6") (pinfunction "D+_1_A6") (pintype "bidirectional"))
      (node (ref "J3") (pin "B6") (pinfunction "D+_2_B6") (pintype "bidirectional"))
      (node (ref "U2") (pin "28") (pinfunction "USBDP_28") (pintype "bidirectional"))
    )
    (net (code "7") (name "EXT_RST_SIG") (class "Default")
      (node (ref "R6") (pin "1") (pinfunction "1_1") (pintype "passive"))
      (node (ref "SW2") (pin "2") (pinfunction "2_2") (pintype "passive"))
    )
    (net (code "8") (name "GND") (class "Default")
      (node (ref "BZ1") (pin "-") (pinfunction "+_-") (pintype "passive"))
      (node (ref "C1") (pin "2") (pinfunction "2_2") (pintype "passive"))
      (node (ref "C10") (pin "2") (pinfunction "2_2") (pintype "passive"))
      (node (ref "C11") (pin "2") (pinfunction "2_2") (pintype "passive"))
      (node (ref "C12") (pin "2") (pinfunction "2_2") (pintype "passive"))
      (node (ref "C13") (pin "2") (pinfunction "2_2") (pintype "passive"))
      (node (ref "C14") (pin "1") (pinfunction "1_1") (pintype "passive"))
      (node (ref "C15") (pin "2") (pinfunction "2_2") (pintype "passive"))
      (node (ref "C16") (pin "2") (pinfunction "2_2") (pintype "passive"))
      (node (ref "C17") (pin "2") (pinfunction "2_2") (pintype "passive"))
      (node (ref "C18") (pin "2") (pinfunction "2_2") (pintype "passive"))
      (node (ref "C19") (pin "2") (pinfunction "2_2") (pintype "passive"))
      (node (ref "C2") (pin "2") (pinfunction "2_2") (pintype "passive"))
      (node (ref "C20") (pin "2") (pinfunction "2_2") (pintype "passive"))
      (node (ref "C21") (pin "2") (pinfunction "2_2") (pintype "passive"))
      (node (ref "C22") (pin "2") (pinfunction "2_2") (pintype "passive"))
      (node (ref "C23") (pin "2") (pinfunction "2_2") (pintype "passive"))
      (node (ref "C24") (pin "2") (pinfunction "2_2") (pintype "passive"))
      (node (ref "C25") (pin "2") (pinfunction "2_2") (pintype "passive"))
      (node (ref "C26") (pin "-") (pinfunction "-_-") (pintype "passive"))
      (node (ref "C3") (pin "-") (pinfunction "-_-") (pintype "passive"))
      (node (ref "C4") (pin "-") (pinfunction "-_-") (pintype "passive"))
      (node (ref "C5") (pin "2") (pinfunction "2_2") (pintype "passive"))
      (node (ref "C6") (pin "2") (pinfunction "2_2") (pintype "passive"))
      (node (ref "C7") (pin "-") (pinfunction "-_-") (pintype "passive"))
      (node (ref "C8") (pin "-") (pinfunction "-_-") (pintype "passive"))
      (node (ref "C9") (pin "-") (pinfunction "-_-") (pintype "passive"))
      (node (ref "D1") (pin "A") (pinfunction "A_A") (pintype "passive"))
      (node (ref "D12") (pin "K") (pinfunction "C_K") (pintype "passive"))
      (node (ref "D2") (pin "K") (pinfunction "C_K") (pintype "passive"))
      (node (ref "EXT_ISP") (pin "6") (pinfunction "6_6") (pintype "passive"))
      (node (ref "EXT_PINS") (pin "13") (pinfunction "13_13") (pintype "passive"))
      (node (ref "EXT_PINS") (pin "15") (pinfunction "15_15") (pintype "passive"))
      (node (ref "ISP_FIRM") (pin "6") (pinfunction "6_6") (pintype "passive"))
      (node (ref "J1") (pin "2") (pinfunction "2_2") (pintype "passive"))
      (node (ref "J1") (pin "3") (pinfunction "3_3") (pintype "passive"))
      (node (ref "J2") (pin "1") (pinfunction "1_1") (pintype "passive"))
      (node (ref "J3") (pin "A1") (pinfunction "GND_A1") (pintype "bidirectional"))
      (node (ref "J3") (pin "A12") (pinfunction "GND_A12") (pintype "bidirectional"))
      (node (ref "J3") (pin "B1") (pinfunction "GND_B1") (pintype "bidirectional"))
      (node (ref "J3") (pin "B12") (pinfunction "GND_B12") (pintype "bidirectional"))
      (node (ref "RST") (pin "1") (pinfunction "1_1") (pintype "passive"))
      (node (ref "RST") (pin "2") (pinfunction "2_2") (pintype "passive"))
      (node (ref "S1") (pin "1") (pinfunction "O_1") (pintype "passive"))
      (node (ref "S10") (pin "3") (pinfunction "P_3") (pintype "passive"))
      (node (ref "S10") (pin "4") (pinfunction "P_4") (pintype "passive"))
      (node (ref "S11") (pin "3") (pinfunction "P_3") (pintype "passive"))
      (node (ref "S11") (pin "4") (pinfunction "P_4") (pintype "passive"))
      (node (ref "S12") (pin "3") (pinfunction "P_3") (pintype "passive"))
      (node (ref "S12") (pin "4") (pinfunction "P_4") (pintype "passive"))
      (node (ref "S2") (pin "1") (pinfunction "O_1") (pintype "passive"))
      (node (ref "S3") (pin "1") (pinfunction "O_1") (pintype "passive"))
      (node (ref "S4") (pin "1") (pinfunction "O_1") (pintype "passive"))
      (node (ref "S5") (pin "1") (pinfunction "O_1") (pintype "passive"))
      (node (ref "S6") (pin "1") (pinfunction "O_1") (pintype "passive"))
      (node (ref "S7") (pin "1") (pinfunction "O_1") (pintype "passive"))
      (node (ref "S8") (pin "1") (pinfunction "O_1") (pintype "passive"))
      (node (ref "S9") (pin "3") (pinfunction "P_3") (pintype "passive"))
      (node (ref "S9") (pin "4") (pinfunction "P_4") (pintype "passive"))
      (node (ref "SW3") (pin "C") (pinfunction "C_C") (pintype "passive"))
      (node (ref "SW3") (pin "E") (pinfunction "E_E") (pintype "passive"))
      (node (ref "U1") (pin "22") (pinfunction "GND_22") (pintype "power_in"))
      (node (ref "U1") (pin "53") (pinfunction "GND_53") (pintype "power_in"))
      (node (ref "U1") (pin "63") (pinfunction "GND_63") (pintype "power_in"))
      (node (ref "U2") (pin "17") (pinfunction "TEST_17") (pintype "bidirectional"))
      (node (ref "U2") (pin "18") (pinfunction "AGND_18") (pintype "power_in"))
      (node (ref "U2") (pin "22") (pinfunction "GND_22") (pintype "power_in"))
      (node (ref "U2") (pin "25") (pinfunction "GND_25") (pintype "power_in"))
      (node (ref "U2") (pin "7") (pinfunction "GND_7") (pintype "power_in"))
      (node (ref "U3") (pin "21") (pinfunction "AGND_21") (pintype "power_in"))
      (node (ref "U3") (pin "3") (pinfunction "GND_3") (pintype "power_in"))
      (node (ref "U3") (pin "5") (pinfunction "GND_5") (pintype "power_in"))
      (node (ref "U4") (pin "3") (pinfunction "GND_3") (pintype "power_in"))
      (node (ref "U4") (pin "5") (pinfunction "EN_5") (pintype "input"))
      (node (ref "U4") (pin "6") (pinfunction "GND_6") (pintype "power_in"))
      (node (ref "U5") (pin "1") (pinfunction "GND/ADJ_1") (pintype "input"))
      (node (ref "U6") (pin "13") (pinfunction "G_13") (pintype "input"))
      (node (ref "U6") (pin "8") (pinfunction "GND_8") (pintype "power_in"))
      (node (ref "U7") (pin "4") (pinfunction "C_4") (pintype "passive"))
      (node (ref "U7") (pin "5") (pinfunction "C_5") (pintype "passive"))
      (node (ref "U7") (pin "6") (pinfunction "C_6") (pintype "passive"))
      (node (ref "U8") (pin "13") (pinfunction "GND_13") (pintype "power_in"))
      (node (ref "U8") (pin "21") (pinfunction "GND_21") (pintype "power_in"))
      (node (ref "U8") (pin "22") (pinfunction "GND_22") (pintype "power_in"))
      (node (ref "VR1") (pin "1") (pinfunction "1_1") (pintype "passive"))
    )
    (net (code "9") (name "Net-(D2-PadA)") (class "Default")
      (node (ref "D2") (pin "A") (pinfunction "A_A") (pintype "passive"))
      (node (ref "R8") (pin "1") (pinfunction "1_1") (pintype "passive"))
    )
    (net (code "10") (name "Net-(D3-A)") (class "Default")
      (node (ref "D3") (pin "P$11") (pinfunction "A_P$11") (pintype "bidirectional"))
      (node (ref "R40") (pin "2") (pinfunction "2_2") (pintype "passive"))
    )
    (net (code "11") (name "Net-(D3-B)") (class "Default")
      (node (ref "D3") (pin "P$7") (pinfunction "B_P$7") (pintype "bidirectional"))
      (node (ref "R41") (pin "2") (pinfunction "2_2") (pintype "passive"))
    )
    (net (code "12") (name "Net-(D3-C)") (class "Default")
      (node (ref "D3") (pin "P$4") (pinfunction "C_P$4") (pintype "bidirectional"))
      (node (ref "R42") (pin "2") (pinfunction "2_2") (pintype "passive"))
    )
    (net (code "13") (name "Net-(D3-C1)") (class "Default")
      (node (ref "D3") (pin "P$12") (pinfunction "C1_P$12") (pintype "bidirectional"))
      (node (ref "Q1") (pin "E") (pinfunction "E_E") (pintype "passive"))
    )
    (net (code "14") (name "Net-(D3-C2)") (class "Default")
      (node (ref "D3") (pin "P$9") (pinfunction "C2_P$9") (pintype "bidirectional"))
      (node (ref "Q2") (pin "E") (pinfunction "E_E") (pintype "passive"))
    )
    (net (code "15") (name "Net-(D3-C3)") (class "Default")
      (node (ref "D3") (pin "P$8") (pinfunction "C3_P$8") (pintype "bidirectional"))
      (node (ref "Q3") (pin "E") (pinfunction "E_E") (pintype "passive"))
    )
    (net (code "16") (name "Net-(D3-C4)") (class "Default")
      (node (ref "D3") (pin "P$6") (pinfunction "C4_P$6") (pintype "bidirectional"))
      (node (ref "Q4") (pin "E") (pinfunction "E_E") (pintype "passive"))
    )
    (net (code "17") (name "Net-(D3-D)") (class "Default")
      (node (ref "D3") (pin "P$2") (pinfunction "D_P$2") (pintype "bidirectional"))
      (node (ref "R43") (pin "2") (pinfunction "2_2") (pintype "passive"))
    )
    (net (code "18") (name "Net-(D3-DP)") (class "Default")
      (node (ref "D3") (pin "P$3") (pinfunction "DP_P$3") (pintype "bidirectional"))
      (node (ref "R47") (pin "2") (pinfunction "2_2") (pintype "passive"))
    )
    (net (code "19") (name "Net-(D3-E)") (class "Default")
      (node (ref "D3") (pin "P$1") (pinfunction "E_P$1") (pintype "bidirectional"))
      (node (ref "R44") (pin "2") (pinfunction "2_2") (pintype "passive"))
    )
    (net (code "20") (name "Net-(D3-F)") (class "Default")
      (node (ref "D3") (pin "P$10") (pinfunction "F_P$10") (pintype "bidirectional"))
      (node (ref "R45") (pin "2") (pinfunction "2_2") (pintype "passive"))
    )
    (net (code "21") (name "Net-(D3-G)") (class "Default")
      (node (ref "D3") (pin "P$5") (pinfunction "G_P$5") (pintype "bidirectional"))
      (node (ref "R46") (pin "2") (pinfunction "2_2") (pintype "passive"))
    )
    (net (code "22") (name "Net-(D4-C)") (class "Default")
      (node (ref "D4") (pin "K") (pinfunction "C_K") (pintype "passive"))
      (node (ref "R10") (pin "1") (pinfunction "1_1") (pintype "passive"))
    )
    (net (code "23") (name "Net-(D5-C)") (class "Default")
      (node (ref "D5") (pin "K") (pinfunction "C_K") (pintype "passive"))
      (node (ref "R11") (pin "1") (pinfunction "1_1") (pintype "passive"))
    )
    (net (code "24") (name "Net-(D6-C)") (class "Default")
      (node (ref "D6") (pin "K") (pinfunction "C_K") (pintype "passive"))
      (node (ref "R12") (pin "1") (pinfunction "1_1") (pintype "passive"))
    )
    (net (code "25") (name "Net-(D7-C)") (class "Default")
      (node (ref "D7") (pin "K") (pinfunction "C_K") (pintype "passive"))
      (node (ref "R13") (pin "1") (pinfunction "1_1") (pintype "passive"))
    )
    (net (code "26") (name "Net-(D8-C)") (class "Default")
      (node (ref "D8") (pin "K") (pinfunction "C_K") (pintype "passive"))
      (node (ref "R14") (pin "1") (pinfunction "1_1") (pintype "passive"))
    )
    (net (code "27") (name "Net-(D9-C)") (class "Default")
      (node (ref "D9") (pin "K") (pinfunction "C_K") (pintype "passive"))
      (node (ref "R15") (pin "1") (pinfunction "1_1") (pintype "passive"))
    )
    (net (code "28") (name "Net-(D10-C)") (class "Default")
      (node (ref "D10") (pin "K") (pinfunction "C_K") (pintype "passive"))
      (node (ref "R16") (pin "1") (pinfunction "1_1") (pintype "passive"))
    )
    (net (code "29") (name "Net-(D11-C)") (class "Default")
      (node (ref "D11") (pin "K") (pinfunction "C_K") (pintype "passive"))
      (node (ref "R17") (pin "1") (pinfunction "1_1") (pintype "passive"))
    )
    (net (code "30") (name "Net-(D12-PadA)") (class "Default")
      (node (ref "D12") (pin "A") (pinfunction "A_A") (pintype "passive"))
      (node (ref "R1") (pin "1") (pinfunction "1_1") (pintype "passive"))
    )
    (net (code "31") (name "Net-(D13-PadA)") (class "Default")
      (node (ref "D13") (pin "A") (pinfunction "A_A") (pintype "passive"))
      (node (ref "R2") (pin "1") (pinfunction "1_1") (pintype "passive"))
    )
    (net (code "32") (name "Net-(EXT_ISP-Pad1)") (class "Default")
      (node (ref "EXT_ISP") (pin "1") (pinfunction "1_1") (pintype "passive"))
      (node (ref "R4") (pin "2") (pinfunction "2_2") (pintype "passive"))
    )
    (net (code "33") (name "Net-(EXT_ISP-Pad2)") (class "Default")
      (node (ref "EXT_ISP") (pin "2") (pinfunction "2_2") (pintype "passive"))
      (node (ref "SEL_VCC") (pin "2") (pinfunction "2_2") (pintype "passive"))
    )
    (net (code "34") (name "Net-(EXT_ISP-Pad3)") (class "Default")
      (node (ref "EXT_ISP") (pin "3") (pinfunction "3_3") (pintype "passive"))
      (node (ref "R5") (pin "2") (pinfunction "2_2") (pintype "passive"))
    )
    (net (code "35") (name "Net-(EXT_ISP-Pad4)") (class "Default")
      (node (ref "EXT_ISP") (pin "4") (pinfunction "4_4") (pintype "passive"))
      (node (ref "R7") (pin "1") (pinfunction "1_1") (pintype "passive"))
    )
    (net (code "36") (name "Net-(EXT_ISP-Pad5)") (class "Default")
      (node (ref "EXT_ISP") (pin "5") (pinfunction "5_5") (pintype "passive"))
      (node (ref "R6") (pin "2") (pinfunction "2_2") (pintype "passive"))
    )
    (net (code "37") (name "Net-(J1-Pad1)") (class "Default")
      (node (ref "J1") (pin "1") (pinfunction "1_1") (pintype "passive"))
      (node (ref "SW1") (pin "COM") (pinfunction "COM_COM") (pintype "passive"))
    )
    (net (code "38") (name "Net-(Q1-PadB)") (class "Default")
      (node (ref "Q1") (pin "B") (pinfunction "B_B") (pintype "passive"))
      (node (ref "R48") (pin "2") (pinfunction "2_2") (pintype "passive"))
    )
    (net (code "39") (name "Net-(Q2-PadB)") (class "Default")
      (node (ref "Q2") (pin "B") (pinfunction "B_B") (pintype "passive"))
      (node (ref "R49") (pin "2") (pinfunction "2_2") (pintype "passive"))
    )
    (net (code "40") (name "Net-(Q3-PadB)") (class "Default")
      (node (ref "Q3") (pin "B") (pinfunction "B_B") (pintype "passive"))
      (node (ref "R50") (pin "2") (pinfunction "2_2") (pintype "passive"))
    )
    (net (code "41") (name "Net-(Q4-PadB)") (class "Default")
      (node (ref "Q4") (pin "B") (pinfunction "B_B") (pintype "passive"))
      (node (ref "R51") (pin "2") (pinfunction "2_2") (pintype "passive"))
    )
    (net (code "42") (name "Net-(S1-P)") (class "Default")
      (node (ref "R18") (pin "1") (pinfunction "1_1") (pintype "passive"))
      (node (ref "S1") (pin "2") (pinfunction "P_2") (pintype "passive"))
    )
    (net (code "43") (name "Net-(S2-P)") (class "Default")
      (node (ref "R19") (pin "1") (pinfunction "1_1") (pintype "passive"))
      (node (ref "S2") (pin "2") (pinfunction "P_2") (pintype "passive"))
    )
    (net (code "44") (name "Net-(S3-P)") (class "Default")
      (node (ref "R20") (pin "1") (pinfunction "1_1") (pintype "passive"))
      (node (ref "S3") (pin "2") (pinfunction "P_2") (pintype "passive"))
    )
    (net (code "45") (name "Net-(S4-P)") (class "Default")
      (node (ref "R21") (pin "1") (pinfunction "1_1") (pintype "passive"))
      (node (ref "S4") (pin "2") (pinfunction "P_2") (pintype "passive"))
    )
    (net (code "46") (name "Net-(S5-P)") (class "Default")
      (node (ref "R22") (pin "1") (pinfunction "1_1") (pintype "passive"))
      (node (ref "S5") (pin "2") (pinfunction "P_2") (pintype "passive"))
    )
    (net (code "47") (name "Net-(S6-P)") (class "Default")
      (node (ref "R23") (pin "1") (pinfunction "1_1") (pintype "passive"))
      (node (ref "S6") (pin "2") (pinfunction "P_2") (pintype "passive"))
    )
    (net (code "48") (name "Net-(S7-P)") (class "Default")
      (node (ref "R24") (pin "1") (pinfunction "1_1") (pintype "passive"))
      (node (ref "S7") (pin "2") (pinfunction "P_2") (pintype "passive"))
    )
    (net (code "49") (name "Net-(S8-P)") (class "Default")
      (node (ref "R25") (pin "1") (pinfunction "1_1") (pintype "passive"))
      (node (ref "S8") (pin "2") (pinfunction "P_2") (pintype "passive"))
    )
    (net (code "50") (name "Net-(U2-3V3OUT)") (class "Default")
      (node (ref "C9") (pin "+") (pinfunction "+_+") (pintype "passive"))
      (node (ref "U2") (pin "26") (pinfunction "3V3OUT_26") (pintype "bidirectional"))
    )
    (net (code "51") (name "Net-(U4-OUT)") (class "Default")
      (node (ref "D1") (pin "C") (pinfunction "C_C") (pintype "passive"))
      (node (ref "L1") (pin "1") (pinfunction "1_1") (pintype "passive"))
      (node (ref "U4") (pin "2") (pinfunction "OUT_2") (pintype "output"))
    )
    (net (code "52") (name "Net-(U6-QA)") (class "Default")
      (node (ref "R40") (pin "1") (pinfunction "1_1") (pintype "passive"))
      (node (ref "U6") (pin "15") (pinfunction "QA_15") (pintype "tri_state"))
    )
    (net (code "53") (name "Net-(U6-QB)") (class "Default")
      (node (ref "R41") (pin "1") (pinfunction "1_1") (pintype "passive"))
      (node (ref "U6") (pin "1") (pinfunction "QB_1") (pintype "tri_state"))
    )
    (net (code "54") (name "Net-(U6-QC)") (class "Default")
      (node (ref "R42") (pin "1") (pinfunction "1_1") (pintype "passive"))
      (node (ref "U6") (pin "2") (pinfunction "QC_2") (pintype "tri_state"))
    )
    (net (code "55") (name "Net-(U6-QD)") (class "Default")
      (node (ref "R43") (pin "1") (pinfunction "1_1") (pintype "passive"))
      (node (ref "U6") (pin "3") (pinfunction "QD_3") (pintype "tri_state"))
    )
    (net (code "56") (name "Net-(U6-QE)") (class "Default")
      (node (ref "R44") (pin "1") (pinfunction "1_1") (pintype "passive"))
      (node (ref "U6") (pin "4") (pinfunction "QE_4") (pintype "tri_state"))
    )
    (net (code "57") (name "Net-(U6-QF)") (class "Default")
      (node (ref "R45") (pin "1") (pinfunction "1_1") (pintype "passive"))
      (node (ref "U6") (pin "5") (pinfunction "QF_5") (pintype "tri_state"))
    )
    (net (code "58") (name "Net-(U6-QG)") (class "Default")
      (node (ref "R46") (pin "1") (pinfunction "1_1") (pintype "passive"))
      (node (ref "U6") (pin "6") (pinfunction "QG_6") (pintype "tri_state"))
    )
    (net (code "59") (name "Net-(U6-QH)") (class "Default")
      (node (ref "R47") (pin "1") (pinfunction "1_1") (pintype "passive"))
      (node (ref "U6") (pin "7") (pinfunction "QH_7") (pintype "tri_state"))
    )
    (net (code "60") (name "Net-(U6-RCK)") (class "Default")
      (node (ref "R39") (pin "2") (pinfunction "2_2") (pintype "passive"))
      (node (ref "U6") (pin "12") (pinfunction "RCK_12") (pintype "input"))
    )
    (net (code "61") (name "Net-(U6-SCK)") (class "Default")
      (node (ref "R38") (pin "2") (pinfunction "2_2") (pintype "passive"))
      (node (ref "U6") (pin "11") (pinfunction "SCK_11") (pintype "input"))
    )
    (net (code "62") (name "Net-(U6-SER)") (class "Default")
      (node (ref "R37") (pin "2") (pinfunction "2_2") (pintype "passive"))
      (node (ref "U6") (pin "14") (pinfunction "SER_14") (pintype "input"))
    )
    (net (code "63") (name "Net-(U7A-A)") (class "Default")
      (node (ref "R32") (pin "1") (pinfunction "1_1") (pintype "passive"))
      (node (ref "U7") (pin "3") (pinfunction "A_3") (pintype "passive"))
    )
    (net (code "64") (name "Net-(U7B-A)") (class "Default")
      (node (ref "R30") (pin "1") (pinfunction "1_1") (pintype "passive"))
      (node (ref "U7") (pin "1") (pinfunction "A_1") (pintype "passive"))
    )
    (net (code "65") (name "Net-(U7C-A)") (class "Default")
      (node (ref "R31") (pin "1") (pinfunction "1_1") (pintype "passive"))
      (node (ref "U7") (pin "2") (pinfunction "A_2") (pintype "passive"))
    )
    (net (code "66") (name "Net-(U8-RX)") (class "Default")
      (node (ref "R29") (pin "2") (pinfunction "2_2") (pintype "passive"))
      (node (ref "U8") (pin "2") (pinfunction "RX_2") (pintype "bidirectional"))
    )
    (net (code "67") (name "PA0") (class "Default")
      (node (ref "R37") (pin "1") (pinfunction "1_1") (pintype "passive"))
      (node (ref "U1") (pin "51") (pinfunction "(AD0)PA0_51") (pintype "bidirectional"))
    )
    (net (code "68") (name "PA1") (class "Default")
      (node (ref "R39") (pin "1") (pinfunction "1_1") (pintype "passive"))
      (node (ref "U1") (pin "50") (pinfunction "(AD1)PA1_50") (pintype "bidirectional"))
    )
    (net (code "69") (name "PA2") (class "Default")
      (node (ref "R38") (pin "1") (pinfunction "1_1") (pintype "passive"))
      (node (ref "U1") (pin "49") (pinfunction "(AD2)PA2_49") (pintype "bidirectional"))
    )
    (net (code "70") (name "PA3") (class "Default")
      (node (ref "R51") (pin "1") (pinfunction "1_1") (pintype "passive"))
      (node (ref "U1") (pin "48") (pinfunction "(AD3)PA3_48") (pintype "bidirectional"))
    )
    (net (code "71") (name "PA4") (class "Default")
      (node (ref "R50") (pin "1") (pinfunction "1_1") (pintype "passive"))
      (node (ref "U1") (pin "47") (pinfunction "(AD4)PA4_47") (pintype "bidirectional"))
    )
    (net (code "72") (name "PA5") (class "Default")
      (node (ref "R49") (pin "1") (pinfunction "1_1") (pintype "passive"))
      (node (ref "U1") (pin "46") (pinfunction "(AD5)PA5_46") (pintype "bidirectional"))
    )
    (net (code "73") (name "PA6") (class "Default")
      (node (ref "R48") (pin "1") (pinfunction "1_1") (pintype "passive"))
      (node (ref "U1") (pin "45") (pinfunction "(AD6)PA6_45") (pintype "bidirectional"))
    )
    (net (code "74") (name "PA7") (class "Default")
      (node (ref "R10") (pin "2") (pinfunction "2_2") (pintype "passive"))
      (node (ref "U1") (pin "44") (pinfunction "(AD7)PA7_44") (pintype "bidirectional"))
    )
    (net (code "75") (name "PB0") (class "Default")
      (node (ref "R11") (pin "2") (pinfunction "2_2") (pintype "passive"))
      (node (ref "U1") (pin "10") (pinfunction "(SS)PB0_10") (pintype "bidirectional"))
    )
    (net (code "76") (name "PB1{slash}SCK") (class "Default")
      (node (ref "ISP_FIRM") (pin "3") (pinfunction "3_3") (pintype "passive"))
      (node (ref "R12") (pin "2") (pinfunction "2_2") (pintype "passive"))
      (node (ref "R5") (pin "1") (pinfunction "1_1") (pintype "passive"))
      (node (ref "U1") (pin "11") (pinfunction "(SCK)PB1_11") (pintype "bidirectional"))
      (node (ref "U3") (pin "17") (pinfunction "PB5(SCK)_17") (pintype "bidirectional"))
    )
    (net (code "77") (name "PB2{slash}MOSI") (class "Default")
      (node (ref "ISP_FIRM") (pin "4") (pinfunction "4_4") (pintype "passive"))
      (node (ref "R13") (pin "2") (pinfunction "2_2") (pintype "passive"))
      (node (ref "R7") (pin "2") (pinfunction "2_2") (pintype "passive"))
      (node (ref "U1") (pin "12") (pinfunction "(MOSI)PB2_12") (pintype "bidirectional"))
      (node (ref "U3") (pin "15") (pinfunction "PB3(MOSI/OC2)_15") (pintype "bidirectional"))
    )
    (net (code "78") (name "PB3{slash}MISO") (class "Default")
      (node (ref "ISP_FIRM") (pin "1") (pinfunction "1_1") (pintype "passive"))
      (node (ref "R14") (pin "2") (pinfunction "2_2") (pintype "passive"))
      (node (ref "R4") (pin "1") (pinfunction "1_1") (pintype "passive"))
      (node (ref "U1") (pin "13") (pinfunction "(MISO)PB3_13") (pintype "bidirectional"))
      (node (ref "U3") (pin "16") (pinfunction "PB4(MISO)_16") (pintype "bidirectional"))
    )
    (net (code "79") (name "PB4") (class "Default")
      (node (ref "BZ1") (pin "+") (pinfunction "-_+") (pintype "passive"))
      (node (ref "U1") (pin "14") (pinfunction "(OC0)PB4_14") (pintype "bidirectional"))
    )
    (net (code "80") (name "PB5") (class "Default")
      (node (ref "R15") (pin "2") (pinfunction "2_2") (pintype "passive"))
      (node (ref "U1") (pin "15") (pinfunction "(OC1A)PB5_15") (pintype "bidirectional"))
    )
    (net (code "81") (name "PB6") (class "Default")
      (node (ref "R16") (pin "2") (pinfunction "2_2") (pintype "passive"))
      (node (ref "U1") (pin "16") (pinfunction "(OC1B)PB6_16") (pintype "bidirectional"))
    )
    (net (code "82") (name "PB7") (class "Default")
      (node (ref "R17") (pin "2") (pinfunction "2_2") (pintype "passive"))
      (node (ref "U1") (pin "17") (pinfunction "(OC2/OC1C)PB7_17") (pintype "bidirectional"))
    )
    (net (code "83") (name "PC0") (class "Default")
      (node (ref "R18") (pin "2") (pinfunction "2_2") (pintype "passive"))
      (node (ref "U1") (pin "35") (pinfunction "(A8)PC0_35") (pintype "output"))
    )
    (net (code "84") (name "PC1") (class "Default")
      (node (ref "R19") (pin "2") (pinfunction "2_2") (pintype "passive"))
      (node (ref "U1") (pin "36") (pinfunction "(A9)PC1_36") (pintype "output"))
    )
    (net (code "85") (name "PC2") (class "Default")
      (node (ref "R20") (pin "2") (pinfunction "2_2") (pintype "passive"))
      (node (ref "U1") (pin "37") (pinfunction "(A10)PC2_37") (pintype "output"))
    )
    (net (code "86") (name "PC3") (class "Default")
      (node (ref "R21") (pin "2") (pinfunction "2_2") (pintype "passive"))
      (node (ref "U1") (pin "38") (pinfunction "(A11)PC3_38") (pintype "output"))
    )
    (net (code "87") (name "PC4") (class "Default")
      (node (ref "R22") (pin "2") (pinfunction "2_2") (pintype "passive"))
      (node (ref "U1") (pin "39") (pinfunction "(A12)PC4_39") (pintype "output"))
    )
    (net (code "88") (name "PC5") (class "Default")
      (node (ref "R23") (pin "2") (pinfunction "2_2") (pintype "passive"))
      (node (ref "U1") (pin "40") (pinfunction "(A13)PC5_40") (pintype "output"))
    )
    (net (code "89") (name "PC6") (class "Default")
      (node (ref "R24") (pin "2") (pinfunction "2_2") (pintype "passive"))
      (node (ref "U1") (pin "41") (pinfunction "(A14)PC6_41") (pintype "output"))
    )
    (net (code "90") (name "PC7") (class "Default")
      (node (ref "R25") (pin "2") (pinfunction "2_2") (pintype "passive"))
      (node (ref "U1") (pin "42") (pinfunction "(A15)PC7_42") (pintype "output"))
    )
    (net (code "91") (name "PD0") (class "Default")
      (node (ref "J2") (pin "4") (pinfunction "4_4") (pintype "passive"))
      (node (ref "U1") (pin "25") (pinfunction "(SCL/INT0)PD0_25") (pintype "bidirectional"))
    )
    (net (code "92") (name "PD1") (class "Default")
      (node (ref "J2") (pin "3") (pinfunction "3_3") (pintype "passive"))
      (node (ref "U1") (pin "26") (pinfunction "(SDA/INT1)PD1_26") (pintype "bidirectional"))
    )
    (net (code "93") (name "PD2") (class "Default")
      (node (ref "EXT_PINS") (pin "18") (pinfunction "18_18") (pintype "passive"))
      (node (ref "U1") (pin "27") (pinfunction "(RXD1/INT2)PD2_27") (pintype "bidirectional"))
    )
    (net (code "94") (name "PD3") (class "Default")
      (node (ref "EXT_PINS") (pin "16") (pinfunction "16_16") (pintype "passive"))
      (node (ref "U1") (pin "28") (pinfunction "(TXD1/INT3)PD3_28") (pintype "bidirectional"))
    )
    (net (code "95") (name "PD4") (class "Default")
      (node (ref "C20") (pin "1") (pinfunction "1_1") (pintype "passive"))
      (node (ref "R33") (pin "1") (pinfunction "1_1") (pintype "passive"))
      (node (ref "S9") (pin "1") (pinfunction "S_1") (pintype "passive"))
      (node (ref "S9") (pin "2") (pinfunction "S_2") (pintype "passive"))
      (node (ref "U1") (pin "29") (pinfunction "(IC1)PD4_29") (pintype "bidirectional"))
    )
    (net (code "96") (name "PD5") (class "Default")
      (node (ref "C21") (pin "1") (pinfunction "1_1") (pintype "passive"))
      (node (ref "R34") (pin "1") (pinfunction "1_1") (pintype "passive"))
      (node (ref "S10") (pin "1") (pinfunction "S_1") (pintype "passive"))
      (node (ref "S10") (pin "2") (pinfunction "S_2") (pintype "passive"))
      (node (ref "U1") (pin "30") (pinfunction "(XCK1)PD5_30") (pintype "bidirectional"))
    )
    (net (code "97") (name "PD6") (class "Default")
      (node (ref "C22") (pin "1") (pinfunction "1_1") (pintype "passive"))
      (node (ref "R35") (pin "1") (pinfunction "1_1") (pintype "passive"))
      (node (ref "S11") (pin "1") (pinfunction "S_1") (pintype "passive"))
      (node (ref "S11") (pin "2") (pinfunction "S_2") (pintype "passive"))
      (node (ref "U1") (pin "31") (pinfunction "(T1)PD6_31") (pintype "bidirectional"))
    )
    (net (code "98") (name "PD7") (class "Default")
      (node (ref "C23") (pin "1") (pinfunction "1_1") (pintype "passive"))
      (node (ref "R36") (pin "1") (pinfunction "1_1") (pintype "passive"))
      (node (ref "S12") (pin "1") (pinfunction "S_1") (pintype "passive"))
      (node (ref "S12") (pin "2") (pinfunction "S_2") (pintype "passive"))
      (node (ref "U1") (pin "32") (pinfunction "(T2)PD7_32") (pintype "bidirectional"))
    )
    (net (code "99") (name "PE0") (class "Default")
      (node (ref "U1") (pin "2") (pinfunction "(RXD/PDI)PE0_2") (pintype "bidirectional"))
      (node (ref "U8") (pin "1") (pinfunction "TX_1") (pintype "bidirectional"))
    )
    (net (code "100") (name "PE1") (class "Default")
      (node (ref "R29") (pin "1") (pinfunction "1_1") (pintype "passive"))
      (node (ref "U1") (pin "3") (pinfunction "(TXD/PDO)PE1_3") (pintype "bidirectional"))
    )
    (net (code "101") (name "PE2") (class "Default")
      (node (ref "C16") (pin "1") (pinfunction "1_1") (pintype "passive"))
      (node (ref "R26") (pin "1") (pinfunction "1_1") (pintype "passive"))
      (node (ref "SW3") (pin "D") (pinfunction "D_D") (pintype "passive"))
      (node (ref "U1") (pin "4") (pinfunction "(XCK0/AIN0)PE2_4") (pintype "bidirectional"))
    )
    (net (code "102") (name "PE3") (class "Default")
      (node (ref "R31") (pin "2") (pinfunction "2_2") (pintype "passive"))
      (node (ref "U1") (pin "5") (pinfunction "(OC3A/AIN1)PE3_5") (pintype "bidirectional"))
    )
    (net (code "103") (name "PE4") (class "Default")
      (node (ref "R30") (pin "2") (pinfunction "2_2") (pintype "passive"))
      (node (ref "U1") (pin "6") (pinfunction "(OC3B/INT4)PE4_6") (pintype "bidirectional"))
    )
    (net (code "104") (name "PE5") (class "Default")
      (node (ref "R32") (pin "2") (pinfunction "2_2") (pintype "passive"))
      (node (ref "U1") (pin "7") (pinfunction "(OC3C/INT5)PE5_7") (pintype "bidirectional"))
    )
    (net (code "105") (name "PE6") (class "Default")
      (node (ref "C17") (pin "1") (pinfunction "1_1") (pintype "passive"))
      (node (ref "R27") (pin "1") (pinfunction "1_1") (pintype "passive"))
      (node (ref "SW3") (pin "B") (pinfunction "B_B") (pintype "passive"))
      (node (ref "U1") (pin "8") (pinfunction "(T3/INT6)PE6_8") (pintype "bidirectional"))
    )
    (net (code "106") (name "PE7") (class "Default")
      (node (ref "C18") (pin "1") (pinfunction "1_1") (pintype "passive"))
      (node (ref "R28") (pin "1") (pinfunction "1_1") (pintype "passive"))
      (node (ref "SW3") (pin "A") (pinfunction "A_A") (pintype "passive"))
      (node (ref "U1") (pin "9") (pinfunction "(IC3/INT7)PE7_9") (pintype "bidirectional"))
    )
    (net (code "107") (name "PF0") (class "Default")
      (node (ref "U1") (pin "61") (pinfunction "PF0(ADC0)_61") (pintype "input"))
      (node (ref "VR1") (pin "2") (pinfunction "2_2") (pintype "passive"))
    )
    (net (code "108") (name "PF1") (class "Default")
      (node (ref "EXT_PINS") (pin "14") (pinfunction "14_14") (pintype "passive"))
      (node (ref "U1") (pin "60") (pinfunction "PF1(ADC1)_60") (pintype "input"))
    )
    (net (code "109") (name "PF2") (class "Default")
      (node (ref "EXT_PINS") (pin "12") (pinfunction "12_12") (pintype "passive"))
      (node (ref "U1") (pin "59") (pinfunction "PF2(ADC2)_59") (pintype "input"))
    )
    (net (code "110") (name "PF3") (class "Default")
      (node (ref "EXT_PINS") (pin "10") (pinfunction "10_10") (pintype "passive"))
      (node (ref "U1") (pin "58") (pinfunction "PF3(ADC3)_58") (pintype "input"))
    )
    (net (code "111") (name "PF4") (class "Default")
      (node (ref "EXT_PINS") (pin "8") (pinfunction "8_8") (pintype "passive"))
      (node (ref "U1") (pin "57") (pinfunction "PF4(ADC4/TCK)_57") (pintype "input"))
    )
    (net (code "112") (name "PF5") (class "Default")
      (node (ref "EXT_PINS") (pin "6") (pinfunction "6_6") (pintype "passive"))
      (node (ref "U1") (pin "56") (pinfunction "PF5(ADC5/TMS)_56") (pintype "input"))
    )
    (net (code "113") (name "PF6") (class "Default")
      (node (ref "EXT_PINS") (pin "4") (pinfunction "4_4") (pintype "passive"))
      (node (ref "U1") (pin "55") (pinfunction "PF6(ADC6/TDO)_55") (pintype "input"))
    )
    (net (code "114") (name "PF7") (class "Default")
      (node (ref "EXT_PINS") (pin "2") (pinfunction "2_2") (pintype "passive"))
      (node (ref "U1") (pin "54") (pinfunction "PF7(ADC7/TDI)_54") (pintype "input"))
    )
    (net (code "115") (name "PG0") (class "Default")
      (node (ref "EXT_PINS") (pin "9") (pinfunction "9_9") (pintype "passive"))
      (node (ref "U1") (pin "33") (pinfunction "PG0(WR)_33") (pintype "bidirectional"))
    )
    (net (code "116") (name "PG1") (class "Default")
      (node (ref "EXT_PINS") (pin "7") (pinfunction "7_7") (pintype "passive"))
      (node (ref "U1") (pin "34") (pinfunction "PG1(RD)_34") (pintype "bidirectional"))
    )
    (net (code "117") (name "PG2") (class "Default")
      (node (ref "EXT_PINS") (pin "5") (pinfunction "5_5") (pintype "passive"))
      (node (ref "U1") (pin "43") (pinfunction "PG2(ALE)_43") (pintype "bidirectional"))
    )
    (net (code "118") (name "PG3") (class "Default")
      (node (ref "EXT_PINS") (pin "3") (pinfunction "3_3") (pintype "passive"))
      (node (ref "U1") (pin "18") (pinfunction "PG3(TOSC2)_18") (pintype "bidirectional"))
    )
    (net (code "119") (name "PG4") (class "Default")
      (node (ref "EXT_PINS") (pin "1") (pinfunction "1_1") (pintype "passive"))
      (node (ref "U1") (pin "19") (pinfunction "PG4(TOSC1)_19") (pintype "bidirectional"))
    )
    (net (code "120") (name "RESET") (class "Default")
      (node (ref "C19") (pin "1") (pinfunction "1_1") (pintype "passive"))
      (node (ref "R9") (pin "1") (pinfunction "1_1") (pintype "passive"))
      (node (ref "RST") (pin "3") (pinfunction "3_3") (pintype "passive"))
      (node (ref "RST") (pin "4") (pinfunction "4_4") (pintype "passive"))
      (node (ref "SW2") (pin "1") (pinfunction "1_1") (pintype "passive"))
      (node (ref "U1") (pin "20") (pinfunction "RESET_20") (pintype "input"))
    )
    (net (code "121") (name "RST_PIN") (class "Default")
      (node (ref "ISP_FIRM") (pin "5") (pinfunction "5_5") (pintype "passive"))
      (node (ref "R3") (pin "1") (pinfunction "1_1") (pintype "passive"))
      (node (ref "U3") (pin "29") (pinfunction "PC6(/RESET)_29") (pintype "bidirectional"))
    )
    (net (code "122") (name "RXD") (class "Default")
      (node (ref "U2") (pin "1") (pinfunction "TXD_1") (pintype "bidirectional"))
      (node (ref "U3") (pin "30") (pinfunction "PD0(RXD)_30") (pintype "bidirectional"))
    )
    (net (code "123") (name "SS_SIG") (class "Default")
      (node (ref "SW2") (pin "COM") (pinfunction "COM_COM") (pintype "passive"))
      (node (ref "U3") (pin "14") (pinfunction "PB2(SS/OC1B)_14") (pintype "bidirectional"))
    )
    (net (code "124") (name "TXD") (class "Default")
      (node (ref "U2") (pin "5") (pinfunction "RXD_5") (pintype "bidirectional"))
      (node (ref "U3") (pin "31") (pinfunction "PD1(TXD)_31") (pintype "bidirectional"))
    )
    (net (code "125") (name "VBUS") (class "Default")
      (node (ref "C10") (pin "1") (pinfunction "1_1") (pintype "passive"))
      (node (ref "C11") (pin "1") (pinfunction "1_1") (pintype "passive"))
      (node (ref "ISP_FIRM") (pin "2") (pinfunction "2_2") (pintype "passive"))
      (node (ref "J3") (pin "A4") (pinfunction "VBUS_A4") (pintype "bidirectional"))
      (node (ref "J3") (pin "A9") (pinfunction "VBUS_A9") (pintype "bidirectional"))
      (node (ref "J3") (pin "B4") (pinfunction "VBUS_B4") (pintype "bidirectional"))
      (node (ref "J3") (pin "B9") (pinfunction "VBUS_B9") (pintype "bidirectional"))
      (node (ref "R1") (pin "2") (pinfunction "2_2") (pintype "passive"))
      (node (ref "R2") (pin "2") (pinfunction "2_2") (pintype "passive"))
      (node (ref "R3") (pin "2") (pinfunction "2_2") (pintype "passive"))
      (node (ref "SEL_VCC") (pin "1") (pinfunction "1_1") (pintype "passive"))
      (node (ref "U2") (pin "23") (pinfunction "VCC_23") (pintype "power_in"))
      (node (ref "U2") (pin "4") (pinfunction "VCCIO_4") (pintype "power_in"))
      (node (ref "U3") (pin "18") (pinfunction "AVCC_18") (pintype "passive"))
      (node (ref "U3") (pin "4") (pinfunction "VCC_4") (pintype "power_in"))
      (node (ref "U3") (pin "6") (pinfunction "VCC_6") (pintype "power_in"))
    )
    (net (code "126") (name "VCC") (class "Default")
      (node (ref "C25") (pin "1") (pinfunction "1_1") (pintype "passive"))
      (node (ref "C26") (pin "+") (pinfunction "+_+") (pintype "passive"))
      (node (ref "C4") (pin "+") (pinfunction "+_+") (pintype "passive"))
      (node (ref "C5") (pin "1") (pinfunction "1_1") (pintype "passive"))
      (node (ref "C6") (pin "1") (pinfunction "1_1") (pintype "passive"))
      (node (ref "C7") (pin "+") (pinfunction "+_+") (pintype "passive"))
      (node (ref "D10") (pin "A") (pinfunction "A_A") (pintype "passive"))
      (node (ref "D11") (pin "A") (pinfunction "A_A") (pintype "passive"))
      (node (ref "D4") (pin "A") (pinfunction "A_A") (pintype "passive"))
      (node (ref "D5") (pin "A") (pinfunction "A_A") (pintype "passive"))
      (node (ref "D6") (pin "A") (pinfunction "A_A") (pintype "passive"))
      (node (ref "D7") (pin "A") (pinfunction "A_A") (pintype "passive"))
      (node (ref "D8") (pin "A") (pinfunction "A_A") (pintype "passive"))
      (node (ref "D9") (pin "A") (pinfunction "A_A") (pintype "passive"))
      (node (ref "EXT_PINS") (pin "19") (pinfunction "19_19") (pintype "passive"))
      (node (ref "J2") (pin "2") (pinfunction "2_2") (pintype "passive"))
      (node (ref "L1") (pin "2") (pinfunction "2_2") (pintype "passive"))
      (node (ref "Q1") (pin "C") (pinfunction "C_C") (pintype "passive"))
      (node (ref "Q2") (pin "C") (pinfunction "C_C") (pintype "passive"))
      (node (ref "Q3") (pin "C") (pinfunction "C_C") (pintype "passive"))
      (node (ref "Q4") (pin "C") (pinfunction "C_C") (pintype "passive"))
      (node (ref "R26") (pin "2") (pinfunction "2_2") (pintype "passive"))
      (node (ref "R27") (pin "2") (pinfunction "2_2") (pintype "passive"))
      (node (ref "R28") (pin "2") (pinfunction "2_2") (pintype "passive"))
      (node (ref "R33") (pin "2") (pinfunction "2_2") (pintype "passive"))
      (node (ref "R35") (pin "2") (pinfunction "2_2") (pintype "passive"))
      (node (ref "R36") (pin "2") (pinfunction "2_2") (pintype "passive"))
      (node (ref "R8") (pin "2") (pinfunction "2_2") (pintype "passive"))
      (node (ref "R9") (pin "2") (pinfunction "2_2") (pintype "passive"))
      (node (ref "S1") (pin "3") (pinfunction "S_3") (pintype "passive"))
      (node (ref "S2") (pin "3") (pinfunction "S_3") (pintype "passive"))
      (node (ref "S3") (pin "3") (pinfunction "S_3") (pintype "passive"))
      (node (ref "S4") (pin "3") (pinfunction "S_3") (pintype "passive"))
      (node (ref "S5") (pin "3") (pinfunction "S_3") (pintype "passive"))
      (node (ref "S6") (pin "3") (pinfunction "S_3") (pintype "passive"))
      (node (ref "S7") (pin "3") (pinfunction "S_3") (pintype "passive"))
      (node (ref "S8") (pin "3") (pinfunction "S_3") (pintype "passive"))
      (node (ref "U1") (pin "21") (pinfunction "VCC_21") (pintype "power_in"))
      (node (ref "U1") (pin "52") (pinfunction "VCC_52") (pintype "power_in"))
      (node (ref "U1") (pin "64") (pinfunction "AVCC_64") (pintype "power_in"))
      (node (ref "U4") (pin "4") (pinfunction "FB_4") (pintype "input"))
      (node (ref "U5") (pin "3") (pinfunction "IN_3") (pintype "input"))
      (node (ref "U6") (pin "10") (pinfunction "SCL_10") (pintype "input"))
      (node (ref "U6") (pin "16") (pinfunction "VCC_16") (pintype "power_in"))
      (node (ref "VR1") (pin "3") (pinfunction "3_3") (pintype "passive"))
    )
    (net (code "127") (name "X1") (class "Default")
      (node (ref "C1") (pin "1") (pinfunction "1_1") (pintype "passive"))
      (node (ref "U3") (pin "7") (pinfunction "PB6(XTAL1/TOSC1)_7") (pintype "bidirectional"))
      (node (ref "Y1") (pin "2") (pinfunction "2_2") (pintype "passive"))
    )
    (net (code "128") (name "X2") (class "Default")
      (node (ref "C2") (pin "1") (pinfunction "1_1") (pintype "passive"))
      (node (ref "U3") (pin "8") (pinfunction "PB7(XTAL2/TOSC2)_8") (pintype "bidirectional"))
      (node (ref "Y1") (pin "1") (pinfunction "1_1") (pintype "passive"))
    )
    (net (code "129") (name "XTAL1") (class "Default")
      (node (ref "C15") (pin "1") (pinfunction "1_1") (pintype "passive"))
      (node (ref "U1") (pin "24") (pinfunction "XTAL1_24") (pintype "bidirectional"))
      (node (ref "Y2") (pin "1") (pinfunction "1_1") (pintype "passive"))
    )
    (net (code "130") (name "XTAL2") (class "Default")
      (node (ref "C14") (pin "2") (pinfunction "2_2") (pintype "passive"))
      (node (ref "U1") (pin "23") (pinfunction "XTAL2_23") (pintype "bidirectional"))
      (node (ref "Y2") (pin "2") (pinfunction "2_2") (pintype "passive"))
    )
    (net (code "131") (name "unconnected-(J3-CC1-PadA5)") (class "Default")
      (node (ref "J3") (pin "A5") (pinfunction "CC1_A5") (pintype "bidirectional"))
    )
    (net (code "132") (name "unconnected-(J3-CC2-PadB5)") (class "Default")
      (node (ref "J3") (pin "B5") (pinfunction "CC2_B5") (pintype "bidirectional"))
    )
    (net (code "133") (name "unconnected-(J3-RX1+-PadB11)") (class "Default")
      (node (ref "J3") (pin "B11") (pinfunction "RX1+_B11") (pintype "bidirectional"))
    )
    (net (code "134") (name "unconnected-(J3-RX1--PadB10)") (class "Default")
      (node (ref "J3") (pin "B10") (pinfunction "RX1-_B10") (pintype "bidirectional"))
    )
    (net (code "135") (name "unconnected-(J3-RX2+-PadA11)") (class "Default")
      (node (ref "J3") (pin "A11") (pinfunction "RX2+_A11") (pintype "bidirectional"))
    )
    (net (code "136") (name "unconnected-(J3-RX2--PadA10)") (class "Default")
      (node (ref "J3") (pin "A10") (pinfunction "RX2-_A10") (pintype "bidirectional"))
    )
    (net (code "137") (name "unconnected-(J3-SBU1-PadA8)") (class "Default")
      (node (ref "J3") (pin "A8") (pinfunction "SBU1_A8") (pintype "bidirectional"))
    )
    (net (code "138") (name "unconnected-(J3-SBU2-PadB8)") (class "Default")
      (node (ref "J3") (pin "B8") (pinfunction "SBU2_B8") (pintype "bidirectional"))
    )
    (net (code "139") (name "unconnected-(J3-TX1+-PadA2)") (class "Default")
      (node (ref "J3") (pin "A2") (pinfunction "TX1+_A2") (pintype "bidirectional"))
    )
    (net (code "140") (name "unconnected-(J3-TX1--PadA3)") (class "Default")
      (node (ref "J3") (pin "A3") (pinfunction "TX1-_A3") (pintype "bidirectional"))
    )
    (net (code "141") (name "unconnected-(J3-TX2+-PadB2)") (class "Default")
      (node (ref "J3") (pin "B2") (pinfunction "TX2+_B2") (pintype "bidirectional"))
    )
    (net (code "142") (name "unconnected-(J3-TX2--PadB3)") (class "Default")
      (node (ref "J3") (pin "B3") (pinfunction "TX2-_B3") (pintype "bidirectional"))
    )
    (net (code "143") (name "unconnected-(R34-Pad2)") (class "Default")
      (node (ref "R34") (pin "2") (pinfunction "2_2") (pintype "passive"))
    )
    (net (code "144") (name "unconnected-(SW1-Pad1)") (class "Default")
      (node (ref "SW1") (pin "1") (pinfunction "1_1") (pintype "passive"))
    )
    (net (code "145") (name "unconnected-(U1-PEN-Pad1)") (class "Default")
      (node (ref "U1") (pin "1") (pinfunction "PEN_1") (pintype "input"))
    )
    (net (code "146") (name "unconnected-(U2-CBUS0-Pad20)") (class "Default")
      (node (ref "U2") (pin "20") (pinfunction "CBUS0_20") (pintype "bidirectional"))
    )
    (net (code "147") (name "unconnected-(U2-CBUS1-Pad21)") (class "Default")
      (node (ref "U2") (pin "21") (pinfunction "CBUS1_21") (pintype "bidirectional"))
    )
    (net (code "148") (name "unconnected-(U2-CBUS2-Pad13)") (class "Default")
      (node (ref "U2") (pin "13") (pinfunction "CBUS2_13") (pintype "bidirectional"))
    )
    (net (code "149") (name "unconnected-(U2-CBUS3-Pad14)") (class "Default")
      (node (ref "U2") (pin "14") (pinfunction "CBUS3_14") (pintype "bidirectional"))
    )
    (net (code "150") (name "unconnected-(U2-CBUS4-Pad12)") (class "Default")
      (node (ref "U2") (pin "12") (pinfunction "CBUS4_12") (pintype "bidirectional"))
    )
    (net (code "151") (name "unconnected-(U2-CTS#-Pad11)") (class "Default")
      (node (ref "U2") (pin "11") (pinfunction "CTS#_11") (pintype "bidirectional"))
    )
    (net (code "152") (name "unconnected-(U2-DCD#-Pad10)") (class "Default")
      (node (ref "U2") (pin "10") (pinfunction "DCD#_10") (pintype "bidirectional"))
    )
    (net (code "153") (name "unconnected-(U2-DSR#-Pad9)") (class "Default")
      (node (ref "U2") (pin "9") (pinfunction "DSR#_9") (pintype "bidirectional"))
    )
    (net (code "154") (name "unconnected-(U2-DTR#-Pad2)") (class "Default")
      (node (ref "U2") (pin "2") (pinfunction "DTR#_2") (pintype "bidirectional"))
    )
    (net (code "155") (name "unconnected-(U2-NC-Pad8)") (class "Default")
      (node (ref "U2") (pin "8") (pinfunction "NC_8") (pintype "no_connect"))
    )
    (net (code "156") (name "unconnected-(U2-NC-Pad19)") (class "Default")
      (node (ref "U2") (pin "19") (pinfunction "NC_19") (pintype "no_connect"))
    )
    (net (code "157") (name "unconnected-(U2-OSCI-Pad16)") (class "Default")
      (node (ref "U2") (pin "16") (pinfunction "OSCI_16") (pintype "bidirectional"))
    )
    (net (code "158") (name "unconnected-(U2-OSCO-Pad15)") (class "Default")
      (node (ref "U2") (pin "15") (pinfunction "OSCO_15") (pintype "bidirectional"))
    )
    (net (code "159") (name "unconnected-(U2-RESET#-Pad24)") (class "Default")
      (node (ref "U2") (pin "24") (pinfunction "RESET#_24") (pintype "bidirectional"))
    )
    (net (code "160") (name "unconnected-(U2-RI#-Pad6)") (class "Default")
      (node (ref "U2") (pin "6") (pinfunction "RI#_6") (pintype "bidirectional"))
    )
    (net (code "161") (name "unconnected-(U2-RTS#-Pad3)") (class "Default")
      (node (ref "U2") (pin "3") (pinfunction "RTS#_3") (pintype "bidirectional"))
    )
    (net (code "162") (name "unconnected-(U3-ADC6-Pad19)") (class "Default")
      (node (ref "U3") (pin "19") (pinfunction "ADC6_19") (pintype "passive"))
    )
    (net (code "163") (name "unconnected-(U3-ADC7-Pad22)") (class "Default")
      (node (ref "U3") (pin "22") (pinfunction "ADC7_22") (pintype "passive"))
    )
    (net (code "164") (name "unconnected-(U3-AREF-Pad20)") (class "Default")
      (node (ref "U3") (pin "20") (pinfunction "AREF_20") (pintype "passive"))
    )
    (net (code "165") (name "unconnected-(U3-PB0(ICP1)-Pad12)") (class "Default")
      (node (ref "U3") (pin "12") (pinfunction "PB0(ICP1)_12") (pintype "bidirectional"))
    )
    (net (code "166") (name "unconnected-(U3-PB1(OC1A)-Pad13)") (class "Default")
      (node (ref "U3") (pin "13") (pinfunction "PB1(OC1A)_13") (pintype "bidirectional"))
    )
    (net (code "167") (name "unconnected-(U3-PC1(ADC1)-Pad24)") (class "Default")
      (node (ref "U3") (pin "24") (pinfunction "PC1(ADC1)_24") (pintype "bidirectional"))
    )
    (net (code "168") (name "unconnected-(U3-PC2(ADC2)-Pad25)") (class "Default")
      (node (ref "U3") (pin "25") (pinfunction "PC2(ADC2)_25") (pintype "bidirectional"))
    )
    (net (code "169") (name "unconnected-(U3-PC3(ADC3)-Pad26)") (class "Default")
      (node (ref "U3") (pin "26") (pinfunction "PC3(ADC3)_26") (pintype "bidirectional"))
    )
    (net (code "170") (name "unconnected-(U3-PC4(ADC4{slash}SDA)-Pad27)") (class "Default")
      (node (ref "U3") (pin "27") (pinfunction "PC4(ADC4/SDA)_27") (pintype "bidirectional"))
    )
    (net (code "171") (name "unconnected-(U3-PC5(ADC5{slash}SCL)-Pad28)") (class "Default")
      (node (ref "U3") (pin "28") (pinfunction "PC5(ADC5/SCL)_28") (pintype "bidirectional"))
    )
    (net (code "172") (name "unconnected-(U3-PD2(INT0)-Pad32)") (class "Default")
      (node (ref "U3") (pin "32") (pinfunction "PD2(INT0)_32") (pintype "bidirectional"))
    )
    (net (code "173") (name "unconnected-(U3-PD3(INT1)-Pad1)") (class "Default")
      (node (ref "U3") (pin "1") (pinfunction "PD3(INT1)_1") (pintype "bidirectional"))
    )
    (net (code "174") (name "unconnected-(U3-PD4(T0{slash}XCK)-Pad2)") (class "Default")
      (node (ref "U3") (pin "2") (pinfunction "PD4(T0/XCK)_2") (pintype "bidirectional"))
    )
    (net (code "175") (name "unconnected-(U3-PD5(T1)-Pad9)") (class "Default")
      (node (ref "U3") (pin "9") (pinfunction "PD5(T1)_9") (pintype "bidirectional"))
    )
    (net (code "176") (name "unconnected-(U3-PD6(AIN0)-Pad10)") (class "Default")
      (node (ref "U3") (pin "10") (pinfunction "PD6(AIN0)_10") (pintype "bidirectional"))
    )
    (net (code "177") (name "unconnected-(U3-PD7(AIN1)-Pad11)") (class "Default")
      (node (ref "U3") (pin "11") (pinfunction "PD7(AIN1)_11") (pintype "bidirectional"))
    )
    (net (code "178") (name "unconnected-(U5-OUT-Pad4)") (class "Default")
      (node (ref "U5") (pin "4") (pinfunction "OUT_4") (pintype "passive"))
    )
    (net (code "179") (name "unconnected-(U6-QH*-Pad9)") (class "Default")
      (node (ref "U6") (pin "9") (pinfunction "QH*_9") (pintype "tri_state"))
    )
    (net (code "180") (name "unconnected-(U8-AI00-Pad9)") (class "Default")
      (node (ref "U8") (pin "9") (pinfunction "AI00_9") (pintype "bidirectional"))
    )
    (net (code "181") (name "unconnected-(U8-AI01-Pad10)") (class "Default")
      (node (ref "U8") (pin "10") (pinfunction "AI01_10") (pintype "bidirectional"))
    )
    (net (code "182") (name "unconnected-(U8-CLK-Pad19)") (class "Default")
      (node (ref "U8") (pin "19") (pinfunction "CLK_19") (pintype "bidirectional"))
    )
    (net (code "183") (name "unconnected-(U8-CSB-Pad16)") (class "Default")
      (node (ref "U8") (pin "16") (pinfunction "CSB_16") (pintype "bidirectional"))
    )
    (net (code "184") (name "unconnected-(U8-CTS-Pad3)") (class "Default")
      (node (ref "U8") (pin "3") (pinfunction "CTS_3") (pintype "bidirectional"))
    )
    (net (code "185") (name "unconnected-(U8-MISO-Pad18)") (class "Default")
      (node (ref "U8") (pin "18") (pinfunction "MISO_18") (pintype "bidirectional"))
    )
    (net (code "186") (name "unconnected-(U8-MOSI-Pad17)") (class "Default")
      (node (ref "U8") (pin "17") (pinfunction "MOSI_17") (pintype "bidirectional"))
    )
    (net (code "187") (name "unconnected-(U8-NC-Pad14)") (class "Default")
      (node (ref "U8") (pin "14") (pinfunction "NC_14") (pintype "bidirectional"))
    )
    (net (code "188") (name "unconnected-(U8-PCM_CLK-Pad5)") (class "Default")
      (node (ref "U8") (pin "5") (pinfunction "PCM_CLK_5") (pintype "bidirectional"))
    )
    (net (code "189") (name "unconnected-(U8-PCM_IN-Pad7)") (class "Default")
      (node (ref "U8") (pin "7") (pinfunction "PCM_IN_7") (pintype "bidirectional"))
    )
    (net (code "190") (name "unconnected-(U8-PCM_OUT-Pad6)") (class "Default")
      (node (ref "U8") (pin "6") (pinfunction "PCM_OUT_6") (pintype "bidirectional"))
    )
    (net (code "191") (name "unconnected-(U8-PCM_SYNC-Pad8)") (class "Default")
      (node (ref "U8") (pin "8") (pinfunction "PCM_SYNC_8") (pintype "bidirectional"))
    )
    (net (code "192") (name "unconnected-(U8-PI00-Pad23)") (class "Default")
      (node (ref "U8") (pin "23") (pinfunction "PI00_23") (pintype "bidirectional"))
    )
    (net (code "193") (name "unconnected-(U8-PI01-Pad24)") (class "Default")
      (node (ref "U8") (pin "24") (pinfunction "PI01_24") (pintype "bidirectional"))
    )
    (net (code "194") (name "unconnected-(U8-PI02-Pad25)") (class "Default")
      (node (ref "U8") (pin "25") (pinfunction "PI02_25") (pintype "bidirectional"))
    )
    (net (code "195") (name "unconnected-(U8-PI03-Pad26)") (class "Default")
      (node (ref "U8") (pin "26") (pinfunction "PI03_26") (pintype "bidirectional"))
    )
    (net (code "196") (name "unconnected-(U8-PI04-Pad27)") (class "Default")
      (node (ref "U8") (pin "27") (pinfunction "PI04_27") (pintype "bidirectional"))
    )
    (net (code "197") (name "unconnected-(U8-PI05-Pad28)") (class "Default")
      (node (ref "U8") (pin "28") (pinfunction "PI05_28") (pintype "bidirectional"))
    )
    (net (code "198") (name "unconnected-(U8-PI06-Pad29)") (class "Default")
      (node (ref "U8") (pin "29") (pinfunction "PI06_29") (pintype "bidirectional"))
    )
    (net (code "199") (name "unconnected-(U8-PI07-Pad30)") (class "Default")
      (node (ref "U8") (pin "30") (pinfunction "PI07_30") (pintype "bidirectional"))
    )
    (net (code "200") (name "unconnected-(U8-PI08-Pad31)") (class "Default")
      (node (ref "U8") (pin "31") (pinfunction "PI08_31") (pintype "bidirectional"))
    )
    (net (code "201") (name "unconnected-(U8-PI09-Pad32)") (class "Default")
      (node (ref "U8") (pin "32") (pinfunction "PI09_32") (pintype "bidirectional"))
    )
    (net (code "202") (name "unconnected-(U8-PI010-Pad33)") (class "Default")
      (node (ref "U8") (pin "33") (pinfunction "PI010_33") (pintype "bidirectional"))
    )
    (net (code "203") (name "unconnected-(U8-PI011-Pad34)") (class "Default")
      (node (ref "U8") (pin "34") (pinfunction "PI011_34") (pintype "bidirectional"))
    )
    (net (code "204") (name "unconnected-(U8-RESET-Pad11)") (class "Default")
      (node (ref "U8") (pin "11") (pinfunction "RESET_11") (pintype "bidirectional"))
    )
    (net (code "205") (name "unconnected-(U8-RTS-Pad4)") (class "Default")
      (node (ref "U8") (pin "4") (pinfunction "RTS_4") (pintype "bidirectional"))
    )
    (net (code "206") (name "unconnected-(U8-USB_D+-Pad20)") (class "Default")
      (node (ref "U8") (pin "20") (pinfunction "USB_D+_20") (pintype "bidirectional"))
    )
    (net (code "207") (name "unconnected-(U8-USB_D--Pad15)") (class "Default")
      (node (ref "U8") (pin "15") (pinfunction "USB_D-_15") (pintype "bidirectional"))
    )
  )
)
